# zadaca3.net
KiCad netlist of a schematic drawn in EAGLE
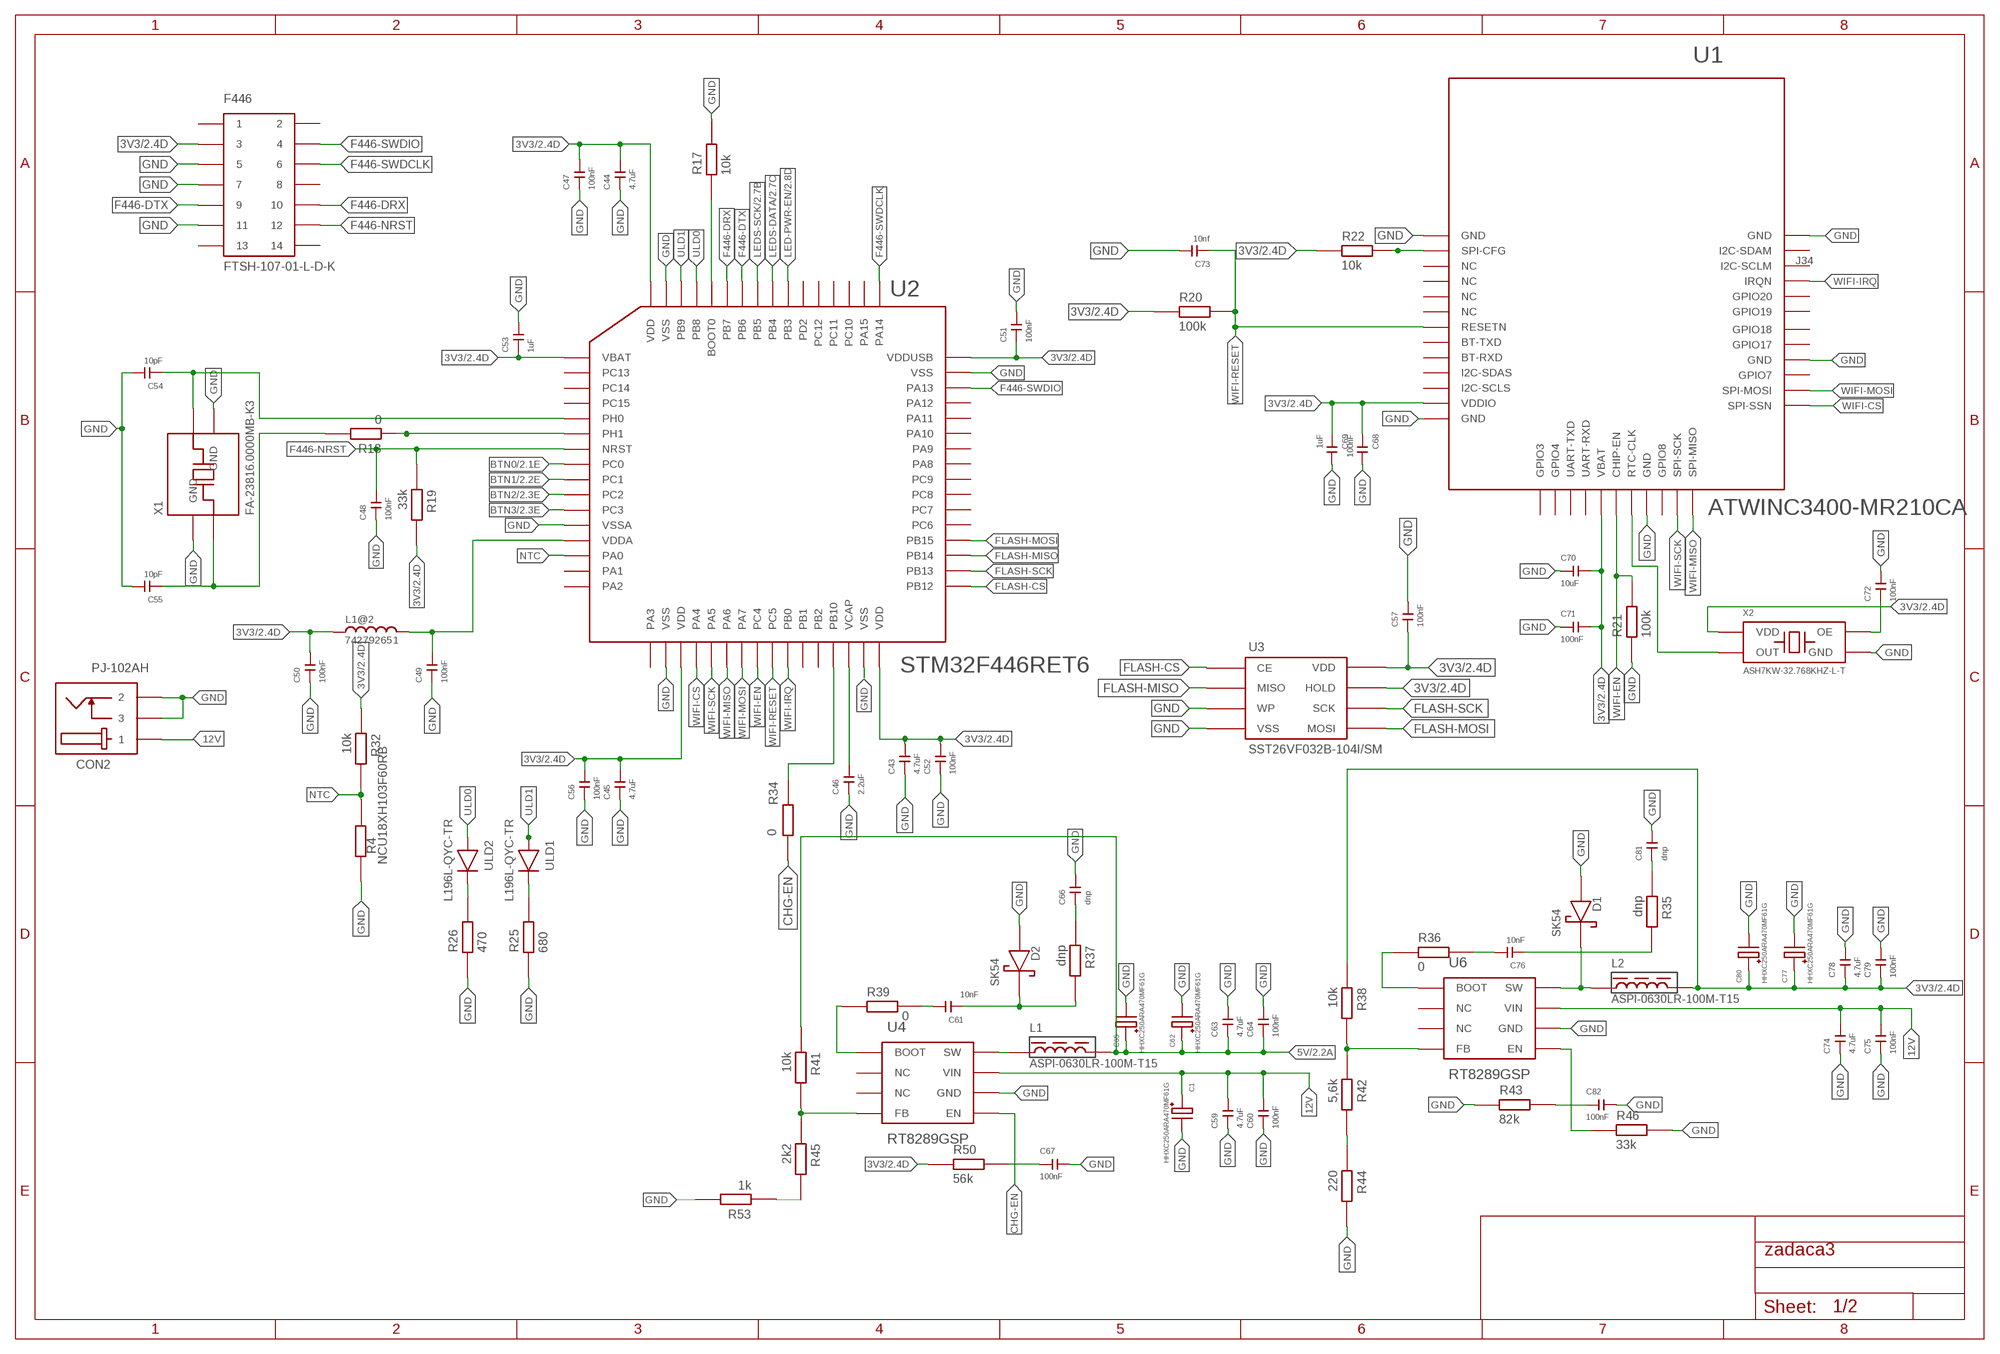
[diagram p0: schematic, sheet 1]
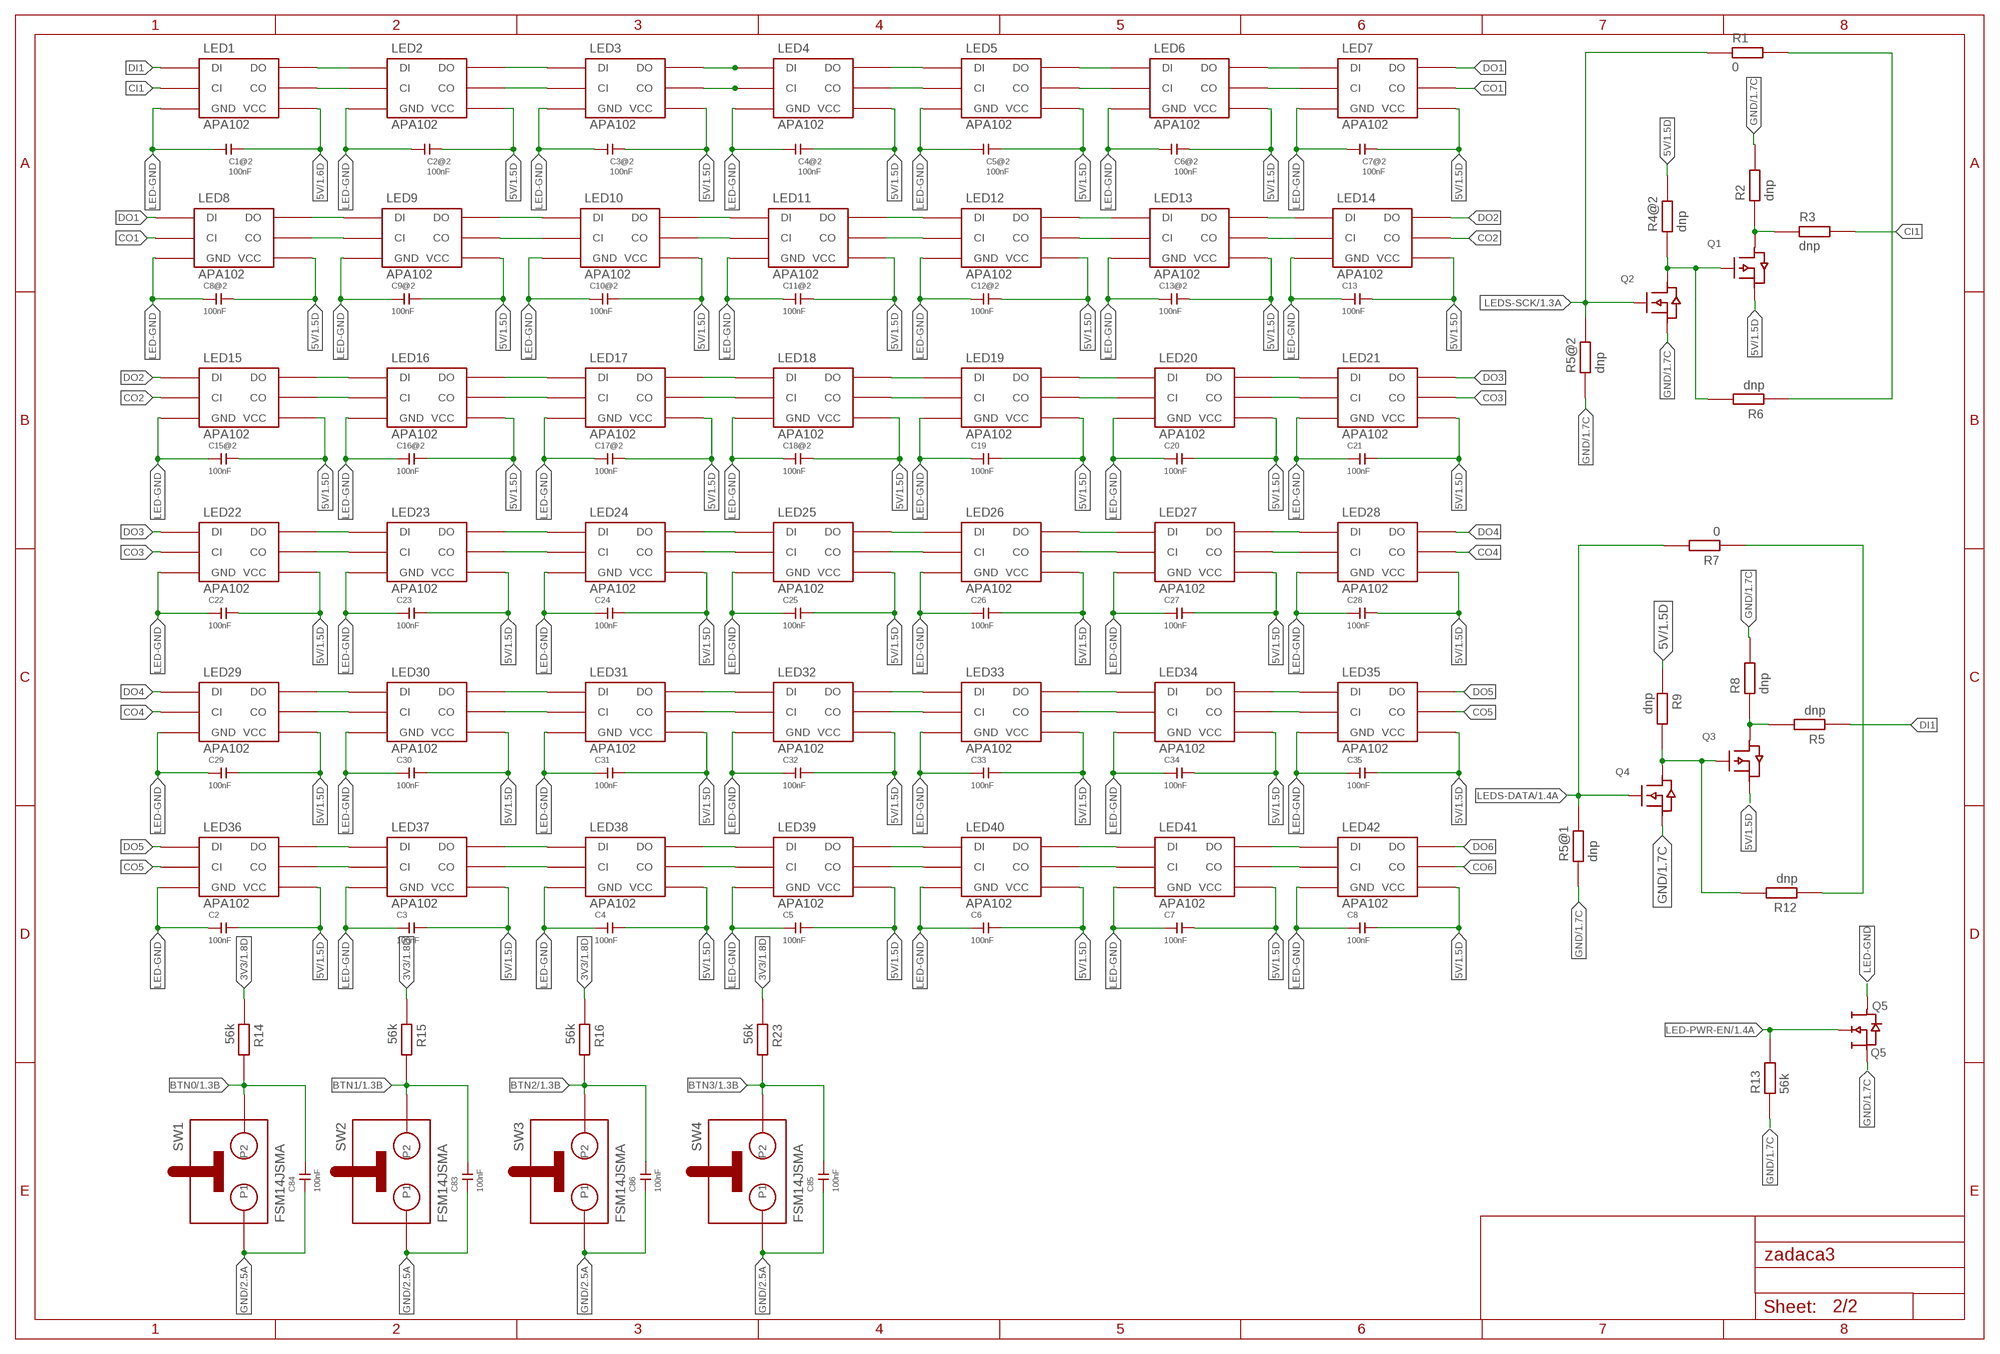
[diagram p1: schematic, sheet 2]

(export (version "E")
  (design (tool "Eeschema 10.0.6"))
  (components
    (comp (ref "C1")
      (value "HHXC250ARA470MF61G")
      (footprint "eagle-import:HHXC250ARA470MF61G")
      (libsource (lib "eagle-import") (part "HHXC250ARA470MF61G"))
    )
    (comp (ref "C43")
      (value "4.7uF")
      (footprint "eagle-import:CAPACITOR-0805-SMD")
      (libsource (lib "eagle-import") (part "CAPACITOR-0805-SMD"))
    )
    (comp (ref "C44")
      (value "4.7uF")
      (footprint "eagle-import:CAPACITOR-0805-SMD")
      (libsource (lib "eagle-import") (part "CAPACITOR-0805-SMD"))
    )
    (comp (ref "C45")
      (value "4.7uF")
      (footprint "eagle-import:CAPACITOR-0805-SMD")
      (libsource (lib "eagle-import") (part "CAPACITOR-0805-SMD"))
    )
    (comp (ref "C46")
      (value "2.2uF")
      (footprint "eagle-import:CAPACITOR-0805-SMD")
      (libsource (lib "eagle-import") (part "CAPACITOR-0805-SMD"))
    )
    (comp (ref "C47")
      (value "100nF")
      (footprint "eagle-import:CAPACITOR-0805-SMD")
      (libsource (lib "eagle-import") (part "CAPACITOR-0805-SMD"))
    )
    (comp (ref "C48")
      (value "100nF")
      (footprint "eagle-import:CAPACITOR-0805-SMD")
      (libsource (lib "eagle-import") (part "CAPACITOR-0805-SMD"))
    )
    (comp (ref "C49")
      (value "100nF")
      (footprint "eagle-import:CAPACITOR-0805-SMD")
      (libsource (lib "eagle-import") (part "CAPACITOR-0805-SMD"))
    )
    (comp (ref "C50")
      (value "100nF")
      (footprint "eagle-import:CAPACITOR-0805-SMD")
      (libsource (lib "eagle-import") (part "CAPACITOR-0805-SMD"))
    )
    (comp (ref "C51")
      (value "100nF")
      (footprint "eagle-import:CAPACITOR-0805-SMD")
      (libsource (lib "eagle-import") (part "CAPACITOR-0805-SMD"))
    )
    (comp (ref "C52")
      (value "100nF")
      (footprint "eagle-import:CAPACITOR-0805-SMD")
      (libsource (lib "eagle-import") (part "CAPACITOR-0805-SMD"))
    )
    (comp (ref "C53")
      (value "1uF")
      (footprint "eagle-import:CAPACITOR-0805-SMD")
      (libsource (lib "eagle-import") (part "CAPACITOR-0805-SMD"))
    )
    (comp (ref "C54")
      (value "10pF")
      (footprint "eagle-import:CAPACITOR-0805-SMD")
      (libsource (lib "eagle-import") (part "CAPACITOR-0805-SMD"))
    )
    (comp (ref "C55")
      (value "10pF")
      (footprint "eagle-import:CAPACITOR-0805-SMD")
      (libsource (lib "eagle-import") (part "CAPACITOR-0805-SMD"))
    )
    (comp (ref "C56")
      (value "100nF")
      (footprint "eagle-import:CAPACITOR-0805-SMD")
      (libsource (lib "eagle-import") (part "CAPACITOR-0805-SMD"))
    )
    (comp (ref "C57")
      (value "100nF")
      (footprint "eagle-import:CAPACITOR-0805-SMD")
      (libsource (lib "eagle-import") (part "CAPACITOR-0805-SMD"))
    )
    (comp (ref "C59")
      (value "4.7uF")
      (footprint "eagle-import:CAPACITOR-0805-SMD")
      (libsource (lib "eagle-import") (part "CAPACITOR-0805-SMD"))
    )
    (comp (ref "C60")
      (value "100nF")
      (footprint "eagle-import:CAPACITOR-0805-SMD")
      (libsource (lib "eagle-import") (part "CAPACITOR-0805-SMD"))
    )
    (comp (ref "C61")
      (value "10nF")
      (footprint "eagle-import:CAPACITOR-0805-SMD")
      (libsource (lib "eagle-import") (part "CAPACITOR-0805-SMD"))
    )
    (comp (ref "C62")
      (value "HHXC250ARA470MF61G")
      (footprint "eagle-import:HHXC250ARA470MF61G")
      (libsource (lib "eagle-import") (part "HHXC250ARA470MF61G"))
    )
    (comp (ref "C63")
      (value "4.7uF")
      (footprint "eagle-import:CAPACITOR-0805-SMD")
      (libsource (lib "eagle-import") (part "CAPACITOR-0805-SMD"))
    )
    (comp (ref "C64")
      (value "100nF")
      (footprint "eagle-import:CAPACITOR-0805-SMD")
      (libsource (lib "eagle-import") (part "CAPACITOR-0805-SMD"))
    )
    (comp (ref "C65")
      (value "HHXC250ARA470MF61G")
      (footprint "eagle-import:HHXC250ARA470MF61G")
      (libsource (lib "eagle-import") (part "HHXC250ARA470MF61G"))
    )
    (comp (ref "C66")
      (value "dnp")
      (footprint "eagle-import:CAPACITOR-0805-SMD")
      (libsource (lib "eagle-import") (part "CAPACITOR-0805-SMD"))
    )
    (comp (ref "C67")
      (value "100nF")
      (footprint "eagle-import:CAPACITOR-0805-SMD")
      (libsource (lib "eagle-import") (part "CAPACITOR-0805-SMD"))
    )
    (comp (ref "C68")
      (value "100nF")
      (footprint "eagle-import:CAPACITOR-0805-SMD")
      (libsource (lib "eagle-import") (part "CAPACITOR-0805-SMD"))
    )
    (comp (ref "C69")
      (value "1uF")
      (footprint "eagle-import:CAPACITOR-0805-SMD")
      (libsource (lib "eagle-import") (part "CAPACITOR-0805-SMD"))
    )
    (comp (ref "C70")
      (value "10uF")
      (footprint "eagle-import:CAPACITOR-0805-SMD")
      (libsource (lib "eagle-import") (part "CAPACITOR-0805-SMD"))
    )
    (comp (ref "C71")
      (value "100nF")
      (footprint "eagle-import:CAPACITOR-0805-SMD")
      (libsource (lib "eagle-import") (part "CAPACITOR-0805-SMD"))
    )
    (comp (ref "C72")
      (value "100nF")
      (footprint "eagle-import:CAPACITOR-0805-SMD")
      (libsource (lib "eagle-import") (part "CAPACITOR-0805-SMD"))
    )
    (comp (ref "C73")
      (value "10nf")
      (footprint "eagle-import:CAPACITOR-0805-SMD")
      (libsource (lib "eagle-import") (part "CAPACITOR-0805-SMD"))
    )
    (comp (ref "C74")
      (value "4.7uF")
      (footprint "eagle-import:CAPACITOR-0805-SMD")
      (libsource (lib "eagle-import") (part "CAPACITOR-0805-SMD"))
    )
    (comp (ref "C75")
      (value "100nF")
      (footprint "eagle-import:CAPACITOR-0805-SMD")
      (libsource (lib "eagle-import") (part "CAPACITOR-0805-SMD"))
    )
    (comp (ref "C76")
      (value "10nF")
      (footprint "eagle-import:CAPACITOR-0805-SMD")
      (libsource (lib "eagle-import") (part "CAPACITOR-0805-SMD"))
    )
    (comp (ref "C77")
      (value "HHXC250ARA470MF61G")
      (footprint "eagle-import:HHXC250ARA470MF61G")
      (libsource (lib "eagle-import") (part "HHXC250ARA470MF61G"))
    )
    (comp (ref "C78")
      (value "4.7uF")
      (footprint "eagle-import:CAPACITOR-0805-SMD")
      (libsource (lib "eagle-import") (part "CAPACITOR-0805-SMD"))
    )
    (comp (ref "C79")
      (value "100nF")
      (footprint "eagle-import:CAPACITOR-0805-SMD")
      (libsource (lib "eagle-import") (part "CAPACITOR-0805-SMD"))
    )
    (comp (ref "C80")
      (value "HHXC250ARA470MF61G")
      (footprint "eagle-import:HHXC250ARA470MF61G")
      (libsource (lib "eagle-import") (part "HHXC250ARA470MF61G"))
    )
    (comp (ref "C81")
      (value "dnp")
      (footprint "eagle-import:CAPACITOR-0805-SMD")
      (libsource (lib "eagle-import") (part "CAPACITOR-0805-SMD"))
    )
    (comp (ref "C82")
      (value "100nF")
      (footprint "eagle-import:CAPACITOR-0805-SMD")
      (libsource (lib "eagle-import") (part "CAPACITOR-0805-SMD"))
    )
    (comp (ref "CON2")
      (value "PJ-102AH")
      (footprint "eagle-import:PJ-102AH")
      (libsource (lib "eagle-import") (part "PJ-102AH"))
    )
    (comp (ref "D1")
      (value "SK54")
      (footprint "eagle-import:SK54")
      (libsource (lib "eagle-import") (part "SK54"))
    )
    (comp (ref "D2")
      (value "SK54")
      (footprint "eagle-import:SK54")
      (libsource (lib "eagle-import") (part "SK54"))
    )
    (comp (ref "F446")
      (value "FTSH-107-01-L-D-K")
      (footprint "eagle-import:FTSH-107-01-L-D-K")
      (libsource (lib "eagle-import") (part "FTSH-107-01-L-D-K"))
    )
    (comp (ref "L1")
      (value "ASPI-0630LR-100M-T15")
      (footprint "eagle-import:ASPI-0630LR-100M-T15")
      (libsource (lib "eagle-import") (part "ASPI-0630LR-100M-T15"))
    )
    (comp (ref "L1@2")
      (value "742792651")
      (footprint "eagle-import:742792651")
      (libsource (lib "eagle-import") (part "742792651"))
    )
    (comp (ref "L2")
      (value "ASPI-0630LR-100M-T15")
      (footprint "eagle-import:ASPI-0630LR-100M-T15")
      (libsource (lib "eagle-import") (part "ASPI-0630LR-100M-T15"))
    )
    (comp (ref "R4")
      (value "NCU18XH103F60RB")
      (footprint "eagle-import:NCU18XH103F60RB")
      (libsource (lib "eagle-import") (part "NCU18XH103F60RB"))
    )
    (comp (ref "R17")
      (value "10k")
      (footprint "eagle-import:RESISTOR-0805-SMD")
      (libsource (lib "eagle-import") (part "RESISTOR-0805-SMD"))
    )
    (comp (ref "R18")
      (value "0")
      (footprint "eagle-import:RESISTOR-0805-SMD")
      (libsource (lib "eagle-import") (part "RESISTOR-0805-SMD"))
    )
    (comp (ref "R19")
      (value "33k")
      (footprint "eagle-import:RESISTOR-0805-SMD")
      (libsource (lib "eagle-import") (part "RESISTOR-0805-SMD"))
    )
    (comp (ref "R20")
      (value "100k")
      (footprint "eagle-import:RESISTOR-0805-SMD")
      (libsource (lib "eagle-import") (part "RESISTOR-0805-SMD"))
    )
    (comp (ref "R21")
      (value "100k")
      (footprint "eagle-import:RESISTOR-0805-SMD")
      (libsource (lib "eagle-import") (part "RESISTOR-0805-SMD"))
    )
    (comp (ref "R22")
      (value "10k")
      (footprint "eagle-import:RESISTOR-0805-SMD")
      (libsource (lib "eagle-import") (part "RESISTOR-0805-SMD"))
    )
    (comp (ref "R25")
      (value "680")
      (footprint "eagle-import:RESISTOR-0805-SMD")
      (libsource (lib "eagle-import") (part "RESISTOR-0805-SMD"))
    )
    (comp (ref "R26")
      (value "470")
      (footprint "eagle-import:RESISTOR-0805-SMD")
      (libsource (lib "eagle-import") (part "RESISTOR-0805-SMD"))
    )
    (comp (ref "R32")
      (value "10k")
      (footprint "eagle-import:RESISTOR-0805-SMD")
      (libsource (lib "eagle-import") (part "RESISTOR-0805-SMD"))
    )
    (comp (ref "R34")
      (value "0")
      (footprint "eagle-import:RESISTOR-0805-SMD")
      (libsource (lib "eagle-import") (part "RESISTOR-0805-SMD"))
    )
    (comp (ref "R35")
      (value "dnp")
      (footprint "eagle-import:RESISTOR-0805-SMD")
      (libsource (lib "eagle-import") (part "RESISTOR-0805-SMD"))
    )
    (comp (ref "R36")
      (value "0")
      (footprint "eagle-import:RESISTOR-0805-SMD")
      (libsource (lib "eagle-import") (part "RESISTOR-0805-SMD"))
    )
    (comp (ref "R37")
      (value "dnp")
      (footprint "eagle-import:RESISTOR-0805-SMD")
      (libsource (lib "eagle-import") (part "RESISTOR-0805-SMD"))
    )
    (comp (ref "R38")
      (value "10k")
      (footprint "eagle-import:RESISTOR-0805-SMD")
      (libsource (lib "eagle-import") (part "RESISTOR-0805-SMD"))
    )
    (comp (ref "R39")
      (value "0")
      (footprint "eagle-import:RESISTOR-0805-SMD")
      (libsource (lib "eagle-import") (part "RESISTOR-0805-SMD"))
    )
    (comp (ref "R41")
      (value "10k")
      (footprint "eagle-import:RESISTOR-0805-SMD")
      (libsource (lib "eagle-import") (part "RESISTOR-0805-SMD"))
    )
    (comp (ref "R42")
      (value "5,6k")
      (footprint "eagle-import:RESISTOR-0805-SMD")
      (libsource (lib "eagle-import") (part "RESISTOR-0805-SMD"))
    )
    (comp (ref "R43")
      (value "82k")
      (footprint "eagle-import:RESISTOR-0805-SMD")
      (libsource (lib "eagle-import") (part "RESISTOR-0805-SMD"))
    )
    (comp (ref "R44")
      (value "220")
      (footprint "eagle-import:RESISTOR-0805-SMD")
      (libsource (lib "eagle-import") (part "RESISTOR-0805-SMD"))
    )
    (comp (ref "R45")
      (value "2k2")
      (footprint "eagle-import:RESISTOR-0805-SMD")
      (libsource (lib "eagle-import") (part "RESISTOR-0805-SMD"))
    )
    (comp (ref "R46")
      (value "33k")
      (footprint "eagle-import:RESISTOR-0805-SMD")
      (libsource (lib "eagle-import") (part "RESISTOR-0805-SMD"))
    )
    (comp (ref "R50")
      (value "56k")
      (footprint "eagle-import:RESISTOR-0805-SMD")
      (libsource (lib "eagle-import") (part "RESISTOR-0805-SMD"))
    )
    (comp (ref "R53")
      (value "1k")
      (footprint "eagle-import:RESISTOR-0805-SMD")
      (libsource (lib "eagle-import") (part "RESISTOR-0805-SMD"))
    )
    (comp (ref "U1")
      (value "ATWINC3400-MR210CA")
      (footprint "eagle-import:ATWINC3400-MR210CA")
      (libsource (lib "eagle-import") (part "ATWINC3400-MR210CA"))
    )
    (comp (ref "U2")
      (value "STM32F446RET6")
      (footprint "eagle-import:STM32F446RET6")
      (libsource (lib "eagle-import") (part "STM32F446RET6"))
    )
    (comp (ref "U3")
      (value "SST26VF032B-104I/SM")
      (footprint "eagle-import:SST26VF032B-104I_SM")
      (libsource (lib "eagle-import") (part "SST26VF032B-104I/SM"))
    )
    (comp (ref "U4")
      (value "RT8289GSP")
      (footprint "eagle-import:RT8289GSP")
      (libsource (lib "eagle-import") (part "RT8289GSP"))
    )
    (comp (ref "U6")
      (value "RT8289GSP")
      (footprint "eagle-import:RT8289GSP")
      (libsource (lib "eagle-import") (part "RT8289GSP"))
    )
    (comp (ref "ULD1")
      (value "L196L-QYC-TR")
      (footprint "eagle-import:L196L-QYC-TR")
      (libsource (lib "eagle-import") (part "L196L-QYC-TR"))
    )
    (comp (ref "ULD2")
      (value "L196L-QYC-TR")
      (footprint "eagle-import:L196L-QYC-TR")
      (libsource (lib "eagle-import") (part "L196L-QYC-TR"))
    )
    (comp (ref "X1")
      (value "FA-23816.0000MB-K3")
      (footprint "eagle-import:FA-23816.0000MB-K3")
      (libsource (lib "eagle-import") (part "FA-23816.0000MB-K3"))
    )
    (comp (ref "X2")
      (value "ASH7KW-32.768KHZ-L-T")
      (footprint "eagle-import:ASH7KW-32.768KHZ-L-T")
      (libsource (lib "eagle-import") (part "ASH7KW-32.768KHZ-L-T"))
    )
    (comp (ref "C1@2")
      (value "100nF")
      (footprint "eagle-import:CAPACITOR-0805-SMD")
      (libsource (lib "eagle-import") (part "CAPACITOR-0805-SMD"))
    )
    (comp (ref "C2")
      (value "100nF")
      (footprint "eagle-import:CAPACITOR-0805-SMD")
      (libsource (lib "eagle-import") (part "CAPACITOR-0805-SMD"))
    )
    (comp (ref "C2@2")
      (value "100nF")
      (footprint "eagle-import:CAPACITOR-0805-SMD")
      (libsource (lib "eagle-import") (part "CAPACITOR-0805-SMD"))
    )
    (comp (ref "C3")
      (value "100nF")
      (footprint "eagle-import:CAPACITOR-0805-SMD")
      (libsource (lib "eagle-import") (part "CAPACITOR-0805-SMD"))
    )
    (comp (ref "C3@2")
      (value "100nF")
      (footprint "eagle-import:CAPACITOR-0805-SMD")
      (libsource (lib "eagle-import") (part "CAPACITOR-0805-SMD"))
    )
    (comp (ref "C4")
      (value "100nF")
      (footprint "eagle-import:CAPACITOR-0805-SMD")
      (libsource (lib "eagle-import") (part "CAPACITOR-0805-SMD"))
    )
    (comp (ref "C4@2")
      (value "100nF")
      (footprint "eagle-import:CAPACITOR-0805-SMD")
      (libsource (lib "eagle-import") (part "CAPACITOR-0805-SMD"))
    )
    (comp (ref "C5")
      (value "100nF")
      (footprint "eagle-import:CAPACITOR-0805-SMD")
      (libsource (lib "eagle-import") (part "CAPACITOR-0805-SMD"))
    )
    (comp (ref "C5@2")
      (value "100nF")
      (footprint "eagle-import:CAPACITOR-0805-SMD")
      (libsource (lib "eagle-import") (part "CAPACITOR-0805-SMD"))
    )
    (comp (ref "C6")
      (value "100nF")
      (footprint "eagle-import:CAPACITOR-0805-SMD")
      (libsource (lib "eagle-import") (part "CAPACITOR-0805-SMD"))
    )
    (comp (ref "C6@2")
      (value "100nF")
      (footprint "eagle-import:CAPACITOR-0805-SMD")
      (libsource (lib "eagle-import") (part "CAPACITOR-0805-SMD"))
    )
    (comp (ref "C7")
      (value "100nF")
      (footprint "eagle-import:CAPACITOR-0805-SMD")
      (libsource (lib "eagle-import") (part "CAPACITOR-0805-SMD"))
    )
    (comp (ref "C7@2")
      (value "100nF")
      (footprint "eagle-import:CAPACITOR-0805-SMD")
      (libsource (lib "eagle-import") (part "CAPACITOR-0805-SMD"))
    )
    (comp (ref "C8")
      (value "100nF")
      (footprint "eagle-import:CAPACITOR-0805-SMD")
      (libsource (lib "eagle-import") (part "CAPACITOR-0805-SMD"))
    )
    (comp (ref "C8@2")
      (value "100nF")
      (footprint "eagle-import:CAPACITOR-0805-SMD")
      (libsource (lib "eagle-import") (part "CAPACITOR-0805-SMD"))
    )
    (comp (ref "C9@2")
      (value "100nF")
      (footprint "eagle-import:CAPACITOR-0805-SMD")
      (libsource (lib "eagle-import") (part "CAPACITOR-0805-SMD"))
    )
    (comp (ref "C10@2")
      (value "100nF")
      (footprint "eagle-import:CAPACITOR-0805-SMD")
      (libsource (lib "eagle-import") (part "CAPACITOR-0805-SMD"))
    )
    (comp (ref "C11@2")
      (value "100nF")
      (footprint "eagle-import:CAPACITOR-0805-SMD")
      (libsource (lib "eagle-import") (part "CAPACITOR-0805-SMD"))
    )
    (comp (ref "C12@2")
      (value "100nF")
      (footprint "eagle-import:CAPACITOR-0805-SMD")
      (libsource (lib "eagle-import") (part "CAPACITOR-0805-SMD"))
    )
    (comp (ref "C13")
      (value "100nF")
      (footprint "eagle-import:CAPACITOR-0805-SMD")
      (libsource (lib "eagle-import") (part "CAPACITOR-0805-SMD"))
    )
    (comp (ref "C13@2")
      (value "100nF")
      (footprint "eagle-import:CAPACITOR-0805-SMD")
      (libsource (lib "eagle-import") (part "CAPACITOR-0805-SMD"))
    )
    (comp (ref "C15@2")
      (value "100nF")
      (footprint "eagle-import:CAPACITOR-0805-SMD")
      (libsource (lib "eagle-import") (part "CAPACITOR-0805-SMD"))
    )
    (comp (ref "C16@2")
      (value "100nF")
      (footprint "eagle-import:CAPACITOR-0805-SMD")
      (libsource (lib "eagle-import") (part "CAPACITOR-0805-SMD"))
    )
    (comp (ref "C17@2")
      (value "100nF")
      (footprint "eagle-import:CAPACITOR-0805-SMD")
      (libsource (lib "eagle-import") (part "CAPACITOR-0805-SMD"))
    )
    (comp (ref "C18@2")
      (value "100nF")
      (footprint "eagle-import:CAPACITOR-0805-SMD")
      (libsource (lib "eagle-import") (part "CAPACITOR-0805-SMD"))
    )
    (comp (ref "C19")
      (value "100nF")
      (footprint "eagle-import:CAPACITOR-0805-SMD")
      (libsource (lib "eagle-import") (part "CAPACITOR-0805-SMD"))
    )
    (comp (ref "C20")
      (value "100nF")
      (footprint "eagle-import:CAPACITOR-0805-SMD")
      (libsource (lib "eagle-import") (part "CAPACITOR-0805-SMD"))
    )
    (comp (ref "C21")
      (value "100nF")
      (footprint "eagle-import:CAPACITOR-0805-SMD")
      (libsource (lib "eagle-import") (part "CAPACITOR-0805-SMD"))
    )
    (comp (ref "C22")
      (value "100nF")
      (footprint "eagle-import:CAPACITOR-0805-SMD")
      (libsource (lib "eagle-import") (part "CAPACITOR-0805-SMD"))
    )
    (comp (ref "C23")
      (value "100nF")
      (footprint "eagle-import:CAPACITOR-0805-SMD")
      (libsource (lib "eagle-import") (part "CAPACITOR-0805-SMD"))
    )
    (comp (ref "C24")
      (value "100nF")
      (footprint "eagle-import:CAPACITOR-0805-SMD")
      (libsource (lib "eagle-import") (part "CAPACITOR-0805-SMD"))
    )
    (comp (ref "C25")
      (value "100nF")
      (footprint "eagle-import:CAPACITOR-0805-SMD")
      (libsource (lib "eagle-import") (part "CAPACITOR-0805-SMD"))
    )
    (comp (ref "C26")
      (value "100nF")
      (footprint "eagle-import:CAPACITOR-0805-SMD")
      (libsource (lib "eagle-import") (part "CAPACITOR-0805-SMD"))
    )
    (comp (ref "C27")
      (value "100nF")
      (footprint "eagle-import:CAPACITOR-0805-SMD")
      (libsource (lib "eagle-import") (part "CAPACITOR-0805-SMD"))
    )
    (comp (ref "C28")
      (value "100nF")
      (footprint "eagle-import:CAPACITOR-0805-SMD")
      (libsource (lib "eagle-import") (part "CAPACITOR-0805-SMD"))
    )
    (comp (ref "C29")
      (value "100nF")
      (footprint "eagle-import:CAPACITOR-0805-SMD")
      (libsource (lib "eagle-import") (part "CAPACITOR-0805-SMD"))
    )
    (comp (ref "C30")
      (value "100nF")
      (footprint "eagle-import:CAPACITOR-0805-SMD")
      (libsource (lib "eagle-import") (part "CAPACITOR-0805-SMD"))
    )
    (comp (ref "C31")
      (value "100nF")
      (footprint "eagle-import:CAPACITOR-0805-SMD")
      (libsource (lib "eagle-import") (part "CAPACITOR-0805-SMD"))
    )
    (comp (ref "C32")
      (value "100nF")
      (footprint "eagle-import:CAPACITOR-0805-SMD")
      (libsource (lib "eagle-import") (part "CAPACITOR-0805-SMD"))
    )
    (comp (ref "C33")
      (value "100nF")
      (footprint "eagle-import:CAPACITOR-0805-SMD")
      (libsource (lib "eagle-import") (part "CAPACITOR-0805-SMD"))
    )
    (comp (ref "C34")
      (value "100nF")
      (footprint "eagle-import:CAPACITOR-0805-SMD")
      (libsource (lib "eagle-import") (part "CAPACITOR-0805-SMD"))
    )
    (comp (ref "C35")
      (value "100nF")
      (footprint "eagle-import:CAPACITOR-0805-SMD")
      (libsource (lib "eagle-import") (part "CAPACITOR-0805-SMD"))
    )
    (comp (ref "C83")
      (value "100nF")
      (footprint "eagle-import:CAPACITOR-0805-SMD")
      (libsource (lib "eagle-import") (part "CAPACITOR-0805-SMD"))
    )
    (comp (ref "C84")
      (value "100nF")
      (footprint "eagle-import:CAPACITOR-0805-SMD")
      (libsource (lib "eagle-import") (part "CAPACITOR-0805-SMD"))
    )
    (comp (ref "C85")
      (value "100nF")
      (footprint "eagle-import:CAPACITOR-0805-SMD")
      (libsource (lib "eagle-import") (part "CAPACITOR-0805-SMD"))
    )
    (comp (ref "C86")
      (value "100nF")
      (footprint "eagle-import:CAPACITOR-0805-SMD")
      (libsource (lib "eagle-import") (part "CAPACITOR-0805-SMD"))
    )
    (comp (ref "LED1")
      (value "APA102")
      (footprint "eagle-import:APA102")
      (libsource (lib "eagle-import") (part "APA102"))
    )
    (comp (ref "LED2")
      (value "APA102")
      (footprint "eagle-import:APA102")
      (libsource (lib "eagle-import") (part "APA102"))
    )
    (comp (ref "LED3")
      (value "APA102")
      (footprint "eagle-import:APA102")
      (libsource (lib "eagle-import") (part "APA102"))
    )
    (comp (ref "LED4")
      (value "APA102")
      (footprint "eagle-import:APA102")
      (libsource (lib "eagle-import") (part "APA102"))
    )
    (comp (ref "LED5")
      (value "APA102")
      (footprint "eagle-import:APA102")
      (libsource (lib "eagle-import") (part "APA102"))
    )
    (comp (ref "LED6")
      (value "APA102")
      (footprint "eagle-import:APA102")
      (libsource (lib "eagle-import") (part "APA102"))
    )
    (comp (ref "LED7")
      (value "APA102")
      (footprint "eagle-import:APA102")
      (libsource (lib "eagle-import") (part "APA102"))
    )
    (comp (ref "LED8")
      (value "APA102")
      (footprint "eagle-import:APA102")
      (libsource (lib "eagle-import") (part "APA102"))
    )
    (comp (ref "LED9")
      (value "APA102")
      (footprint "eagle-import:APA102")
      (libsource (lib "eagle-import") (part "APA102"))
    )
    (comp (ref "LED10")
      (value "APA102")
      (footprint "eagle-import:APA102")
      (libsource (lib "eagle-import") (part "APA102"))
    )
    (comp (ref "LED11")
      (value "APA102")
      (footprint "eagle-import:APA102")
      (libsource (lib "eagle-import") (part "APA102"))
    )
    (comp (ref "LED12")
      (value "APA102")
      (footprint "eagle-import:APA102")
      (libsource (lib "eagle-import") (part "APA102"))
    )
    (comp (ref "LED13")
      (value "APA102")
      (footprint "eagle-import:APA102")
      (libsource (lib "eagle-import") (part "APA102"))
    )
    (comp (ref "LED14")
      (value "APA102")
      (footprint "eagle-import:APA102")
      (libsource (lib "eagle-import") (part "APA102"))
    )
    (comp (ref "LED15")
      (value "APA102")
      (footprint "eagle-import:APA102")
      (libsource (lib "eagle-import") (part "APA102"))
    )
    (comp (ref "LED16")
      (value "APA102")
      (footprint "eagle-import:APA102")
      (libsource (lib "eagle-import") (part "APA102"))
    )
    (comp (ref "LED17")
      (value "APA102")
      (footprint "eagle-import:APA102")
      (libsource (lib "eagle-import") (part "APA102"))
    )
    (comp (ref "LED18")
      (value "APA102")
      (footprint "eagle-import:APA102")
      (libsource (lib "eagle-import") (part "APA102"))
    )
    (comp (ref "LED19")
      (value "APA102")
      (footprint "eagle-import:APA102")
      (libsource (lib "eagle-import") (part "APA102"))
    )
    (comp (ref "LED20")
      (value "APA102")
      (footprint "eagle-import:APA102")
      (libsource (lib "eagle-import") (part "APA102"))
    )
    (comp (ref "LED21")
      (value "APA102")
      (footprint "eagle-import:APA102")
      (libsource (lib "eagle-import") (part "APA102"))
    )
    (comp (ref "LED22")
      (value "APA102")
      (footprint "eagle-import:APA102")
      (libsource (lib "eagle-import") (part "APA102"))
    )
    (comp (ref "LED23")
      (value "APA102")
      (footprint "eagle-import:APA102")
      (libsource (lib "eagle-import") (part "APA102"))
    )
    (comp (ref "LED24")
      (value "APA102")
      (footprint "eagle-import:APA102")
      (libsource (lib "eagle-import") (part "APA102"))
    )
    (comp (ref "LED25")
      (value "APA102")
      (footprint "eagle-import:APA102")
      (libsource (lib "eagle-import") (part "APA102"))
    )
    (comp (ref "LED26")
      (value "APA102")
      (footprint "eagle-import:APA102")
      (libsource (lib "eagle-import") (part "APA102"))
    )
    (comp (ref "LED27")
      (value "APA102")
      (footprint "eagle-import:APA102")
      (libsource (lib "eagle-import") (part "APA102"))
    )
    (comp (ref "LED28")
      (value "APA102")
      (footprint "eagle-import:APA102")
      (libsource (lib "eagle-import") (part "APA102"))
    )
    (comp (ref "LED29")
      (value "APA102")
      (footprint "eagle-import:APA102")
      (libsource (lib "eagle-import") (part "APA102"))
    )
    (comp (ref "LED30")
      (value "APA102")
      (footprint "eagle-import:APA102")
      (libsource (lib "eagle-import") (part "APA102"))
    )
    (comp (ref "LED31")
      (value "APA102")
      (footprint "eagle-import:APA102")
      (libsource (lib "eagle-import") (part "APA102"))
    )
    (comp (ref "LED32")
      (value "APA102")
      (footprint "eagle-import:APA102")
      (libsource (lib "eagle-import") (part "APA102"))
    )
    (comp (ref "LED33")
      (value "APA102")
      (footprint "eagle-import:APA102")
      (libsource (lib "eagle-import") (part "APA102"))
    )
    (comp (ref "LED34")
      (value "APA102")
      (footprint "eagle-import:APA102")
      (libsource (lib "eagle-import") (part "APA102"))
    )
    (comp (ref "LED35")
      (value "APA102")
      (footprint "eagle-import:APA102")
      (libsource (lib "eagle-import") (part "APA102"))
    )
    (comp (ref "LED36")
      (value "APA102")
      (footprint "eagle-import:APA102")
      (libsource (lib "eagle-import") (part "APA102"))
    )
    (comp (ref "LED37")
      (value "APA102")
      (footprint "eagle-import:APA102")
      (libsource (lib "eagle-import") (part "APA102"))
    )
    (comp (ref "LED38")
      (value "APA102")
      (footprint "eagle-import:APA102")
      (libsource (lib "eagle-import") (part "APA102"))
    )
    (comp (ref "LED39")
      (value "APA102")
      (footprint "eagle-import:APA102")
      (libsource (lib "eagle-import") (part "APA102"))
    )
    (comp (ref "LED40")
      (value "APA102")
      (footprint "eagle-import:APA102")
      (libsource (lib "eagle-import") (part "APA102"))
    )
    (comp (ref "LED41")
      (value "APA102")
      (footprint "eagle-import:APA102")
      (libsource (lib "eagle-import") (part "APA102"))
    )
    (comp (ref "LED42")
      (value "APA102")
      (footprint "eagle-import:APA102")
      (libsource (lib "eagle-import") (part "APA102"))
    )
    (comp (ref "Q1")
      (value "NPN")
      (footprint "eagle-import:NPN")
      (libsource (lib "eagle-import") (part "NPN"))
    )
    (comp (ref "Q2")
      (value "PNP")
      (footprint "eagle-import:PNP")
      (libsource (lib "eagle-import") (part "PNP"))
    )
    (comp (ref "Q3")
      (value "NPN")
      (footprint "eagle-import:NPN")
      (libsource (lib "eagle-import") (part "NPN"))
    )
    (comp (ref "Q4")
      (value "PNP")
      (footprint "eagle-import:PNP")
      (libsource (lib "eagle-import") (part "PNP"))
    )
    (comp (ref "Q5")
      (value "DMN6068LK3-13")
      (footprint "eagle-import:DMN6068LK3-13")
      (libsource (lib "eagle-import") (part "DMN6068LK3-13"))
    )
    (comp (ref "R1")
      (value "0")
      (footprint "eagle-import:RESISTOR-0805-SMD")
      (libsource (lib "eagle-import") (part "RESISTOR-0805-SMD"))
    )
    (comp (ref "R2")
      (value "dnp")
      (footprint "eagle-import:RESISTOR-0805-SMD")
      (libsource (lib "eagle-import") (part "RESISTOR-0805-SMD"))
    )
    (comp (ref "R3")
      (value "dnp")
      (footprint "eagle-import:RESISTOR-0805-SMD")
      (libsource (lib "eagle-import") (part "RESISTOR-0805-SMD"))
    )
    (comp (ref "R4@2")
      (value "dnp")
      (footprint "eagle-import:RESISTOR-0805-SMD")
      (libsource (lib "eagle-import") (part "RESISTOR-0805-SMD"))
    )
    (comp (ref "R5")
      (value "dnp")
      (footprint "eagle-import:RESISTOR-0805-SMD")
      (libsource (lib "eagle-import") (part "RESISTOR-0805-SMD"))
    )
    (comp (ref "R5@1")
      (value "dnp")
      (footprint "eagle-import:RESISTOR-0805-SMD")
      (libsource (lib "eagle-import") (part "RESISTOR-0805-SMD"))
    )
    (comp (ref "R5@2")
      (value "dnp")
      (footprint "eagle-import:RESISTOR-0805-SMD")
      (libsource (lib "eagle-import") (part "RESISTOR-0805-SMD"))
    )
    (comp (ref "R6")
      (value "dnp")
      (footprint "eagle-import:RESISTOR-0805-SMD")
      (libsource (lib "eagle-import") (part "RESISTOR-0805-SMD"))
    )
    (comp (ref "R7")
      (value "0")
      (footprint "eagle-import:RESISTOR-0805-SMD")
      (libsource (lib "eagle-import") (part "RESISTOR-0805-SMD"))
    )
    (comp (ref "R8")
      (value "dnp")
      (footprint "eagle-import:RESISTOR-0805-SMD")
      (libsource (lib "eagle-import") (part "RESISTOR-0805-SMD"))
    )
    (comp (ref "R9")
      (value "dnp")
      (footprint "eagle-import:RESISTOR-0805-SMD")
      (libsource (lib "eagle-import") (part "RESISTOR-0805-SMD"))
    )
    (comp (ref "R12")
      (value "dnp")
      (footprint "eagle-import:RESISTOR-0805-SMD")
      (libsource (lib "eagle-import") (part "RESISTOR-0805-SMD"))
    )
    (comp (ref "R13")
      (value "56k")
      (footprint "eagle-import:RESISTOR-0805-SMD")
      (libsource (lib "eagle-import") (part "RESISTOR-0805-SMD"))
    )
    (comp (ref "R14")
      (value "56k")
      (footprint "eagle-import:RESISTOR-0805-SMD")
      (libsource (lib "eagle-import") (part "RESISTOR-0805-SMD"))
    )
    (comp (ref "R15")
      (value "56k")
      (footprint "eagle-import:RESISTOR-0805-SMD")
      (libsource (lib "eagle-import") (part "RESISTOR-0805-SMD"))
    )
    (comp (ref "R16")
      (value "56k")
      (footprint "eagle-import:RESISTOR-0805-SMD")
      (libsource (lib "eagle-import") (part "RESISTOR-0805-SMD"))
    )
    (comp (ref "R23")
      (value "56k")
      (footprint "eagle-import:RESISTOR-0805-SMD")
      (libsource (lib "eagle-import") (part "RESISTOR-0805-SMD"))
    )
    (comp (ref "SW1")
      (value "FSM14JSMA")
      (footprint "eagle-import:FSM14JSMAS")
      (libsource (lib "eagle-import") (part "FSM14JSMA"))
    )
    (comp (ref "SW2")
      (value "FSM14JSMA")
      (footprint "eagle-import:FSM14JSMAS")
      (libsource (lib "eagle-import") (part "FSM14JSMA"))
    )
    (comp (ref "SW3")
      (value "FSM14JSMA")
      (footprint "eagle-import:FSM14JSMAS")
      (libsource (lib "eagle-import") (part "FSM14JSMA"))
    )
    (comp (ref "SW4")
      (value "FSM14JSMA")
      (footprint "eagle-import:FSM14JSMAS")
      (libsource (lib "eagle-import") (part "FSM14JSMA"))
    )
  )
  (nets
    (net (code "1") (name "3V3") (class "Default")
      (node (ref "C43") (pin "P2") (pinfunction "P2_P2") (pintype "bidirectional"))
      (node (ref "C44") (pin "P2") (pinfunction "P2_P2") (pintype "bidirectional"))
      (node (ref "C45") (pin "P2") (pinfunction "P2_P2") (pintype "bidirectional"))
      (node (ref "C47") (pin "P2") (pinfunction "P2_P2") (pintype "bidirectional"))
      (node (ref "C50") (pin "P2") (pinfunction "P2_P2") (pintype "bidirectional"))
      (node (ref "C51") (pin "P1") (pinfunction "P1_P1") (pintype "bidirectional"))
      (node (ref "C52") (pin "P2") (pinfunction "P2_P2") (pintype "bidirectional"))
      (node (ref "C53") (pin "P1") (pinfunction "P1_P1") (pintype "bidirectional"))
      (node (ref "C56") (pin "P2") (pinfunction "P2_P2") (pintype "bidirectional"))
      (node (ref "C57") (pin "P1") (pinfunction "P1_P1") (pintype "bidirectional"))
      (node (ref "C68") (pin "P1") (pinfunction "P1_P1") (pintype "bidirectional"))
      (node (ref "C69") (pin "P1") (pinfunction "P1_P1") (pintype "bidirectional"))
      (node (ref "C70") (pin "P2") (pinfunction "P2_P2") (pintype "bidirectional"))
      (node (ref "C71") (pin "P2") (pinfunction "P2_P2") (pintype "bidirectional"))
      (node (ref "C77") (pin "2") (pinfunction "P1_2") (pintype "bidirectional"))
      (node (ref "C78") (pin "P1") (pinfunction "P1_P1") (pintype "bidirectional"))
      (node (ref "C79") (pin "P1") (pinfunction "P1_P1") (pintype "bidirectional"))
      (node (ref "C80") (pin "2") (pinfunction "P1_2") (pintype "bidirectional"))
      (node (ref "F446") (pin "3") (pinfunction "3_3") (pintype "bidirectional"))
      (node (ref "L1@2") (pin "P1") (pinfunction "P1_P1") (pintype "bidirectional"))
      (node (ref "L2") (pin "2") (pinfunction "P2_2") (pintype "bidirectional"))
      (node (ref "R14") (pin "P1") (pinfunction "P1_P1") (pintype "bidirectional"))
      (node (ref "R15") (pin "P1") (pinfunction "P1_P1") (pintype "bidirectional"))
      (node (ref "R16") (pin "P1") (pinfunction "P1_P1") (pintype "bidirectional"))
      (node (ref "R19") (pin "P2") (pinfunction "P2_P2") (pintype "bidirectional"))
      (node (ref "R20") (pin "P1") (pinfunction "P1_P1") (pintype "bidirectional"))
      (node (ref "R22") (pin "P1") (pinfunction "P1_P1") (pintype "bidirectional"))
      (node (ref "R23") (pin "P1") (pinfunction "P1_P1") (pintype "bidirectional"))
      (node (ref "R32") (pin "P1") (pinfunction "P1_P1") (pintype "bidirectional"))
      (node (ref "R38") (pin "P1") (pinfunction "P1_P1") (pintype "bidirectional"))
      (node (ref "R50") (pin "P1") (pinfunction "P1_P1") (pintype "bidirectional"))
      (node (ref "U1") (pin "J12") (pinfunction "VDDIO_J12") (pintype "bidirectional"))
      (node (ref "U1") (pin "J18") (pinfunction "VBAT_J18") (pintype "bidirectional"))
      (node (ref "U2") (pin "1") (pinfunction "VBAT_1") (pintype "bidirectional"))
      (node (ref "U2") (pin "19") (pinfunction "VDD_19") (pintype "bidirectional"))
      (node (ref "U2") (pin "32") (pinfunction "VDD_32") (pintype "bidirectional"))
      (node (ref "U2") (pin "48") (pinfunction "VDD_48") (pintype "bidirectional"))
      (node (ref "U2") (pin "64") (pinfunction "VDDUSB_64") (pintype "bidirectional"))
      (node (ref "U3") (pin "7") (pinfunction "HOLD_7") (pintype "bidirectional"))
      (node (ref "U3") (pin "8") (pinfunction "VDD_8") (pintype "bidirectional"))
      (node (ref "X2") (pin "4") (pinfunction "VDD_4") (pintype "bidirectional"))
    )
    (net (code "2") (name "5V") (class "Default")
      (node (ref "C1@2") (pin "P2") (pinfunction "P2_P2") (pintype "bidirectional"))
      (node (ref "C62") (pin "2") (pinfunction "P1_2") (pintype "bidirectional"))
      (node (ref "C63") (pin "P1") (pinfunction "P1_P1") (pintype "bidirectional"))
      (node (ref "C64") (pin "P1") (pinfunction "P1_P1") (pintype "bidirectional"))
      (node (ref "C65") (pin "2") (pinfunction "P1_2") (pintype "bidirectional"))
      (node (ref "L1") (pin "2") (pinfunction "P2_2") (pintype "bidirectional"))
      (node (ref "LED1") (pin "5") (pinfunction "VCC_5") (pintype "bidirectional"))
      (node (ref "R41") (pin "P1") (pinfunction "P1_P1") (pintype "bidirectional"))
    )
    (net (code "3") (name "5V{slash}1.5D") (class "Default")
      (node (ref "C10@2") (pin "P2") (pinfunction "P2_P2") (pintype "bidirectional"))
      (node (ref "C11@2") (pin "P2") (pinfunction "P2_P2") (pintype "bidirectional"))
      (node (ref "C12@2") (pin "P2") (pinfunction "P2_P2") (pintype "bidirectional"))
      (node (ref "C13") (pin "P2") (pinfunction "P2_P2") (pintype "bidirectional"))
      (node (ref "C13@2") (pin "P2") (pinfunction "P2_P2") (pintype "bidirectional"))
      (node (ref "C15@2") (pin "P2") (pinfunction "P2_P2") (pintype "bidirectional"))
      (node (ref "C16@2") (pin "P2") (pinfunction "P2_P2") (pintype "bidirectional"))
      (node (ref "C17@2") (pin "P2") (pinfunction "P2_P2") (pintype "bidirectional"))
      (node (ref "C18@2") (pin "P2") (pinfunction "P2_P2") (pintype "bidirectional"))
      (node (ref "C19") (pin "P2") (pinfunction "P2_P2") (pintype "bidirectional"))
      (node (ref "C2") (pin "P2") (pinfunction "P2_P2") (pintype "bidirectional"))
      (node (ref "C20") (pin "P2") (pinfunction "P2_P2") (pintype "bidirectional"))
      (node (ref "C21") (pin "P2") (pinfunction "P2_P2") (pintype "bidirectional"))
      (node (ref "C22") (pin "P2") (pinfunction "P2_P2") (pintype "bidirectional"))
      (node (ref "C23") (pin "P2") (pinfunction "P2_P2") (pintype "bidirectional"))
      (node (ref "C24") (pin "P2") (pinfunction "P2_P2") (pintype "bidirectional"))
      (node (ref "C25") (pin "P2") (pinfunction "P2_P2") (pintype "bidirectional"))
      (node (ref "C26") (pin "P2") (pinfunction "P2_P2") (pintype "bidirectional"))
      (node (ref "C27") (pin "P2") (pinfunction "P2_P2") (pintype "bidirectional"))
      (node (ref "C28") (pin "P2") (pinfunction "P2_P2") (pintype "bidirectional"))
      (node (ref "C29") (pin "P2") (pinfunction "P2_P2") (pintype "bidirectional"))
      (node (ref "C2@2") (pin "P2") (pinfunction "P2_P2") (pintype "bidirectional"))
      (node (ref "C3") (pin "P2") (pinfunction "P2_P2") (pintype "bidirectional"))
      (node (ref "C30") (pin "P2") (pinfunction "P2_P2") (pintype "bidirectional"))
      (node (ref "C31") (pin "P2") (pinfunction "P2_P2") (pintype "bidirectional"))
      (node (ref "C32") (pin "P2") (pinfunction "P2_P2") (pintype "bidirectional"))
      (node (ref "C33") (pin "P2") (pinfunction "P2_P2") (pintype "bidirectional"))
      (node (ref "C34") (pin "P2") (pinfunction "P2_P2") (pintype "bidirectional"))
      (node (ref "C35") (pin "P2") (pinfunction "P2_P2") (pintype "bidirectional"))
      (node (ref "C3@2") (pin "P2") (pinfunction "P2_P2") (pintype "bidirectional"))
      (node (ref "C4") (pin "P2") (pinfunction "P2_P2") (pintype "bidirectional"))
      (node (ref "C4@2") (pin "P2") (pinfunction "P2_P2") (pintype "bidirectional"))
      (node (ref "C5") (pin "P2") (pinfunction "P2_P2") (pintype "bidirectional"))
      (node (ref "C5@2") (pin "P2") (pinfunction "P2_P2") (pintype "bidirectional"))
      (node (ref "C6") (pin "P2") (pinfunction "P2_P2") (pintype "bidirectional"))
      (node (ref "C6@2") (pin "P2") (pinfunction "P2_P2") (pintype "bidirectional"))
      (node (ref "C7") (pin "P2") (pinfunction "P2_P2") (pintype "bidirectional"))
      (node (ref "C7@2") (pin "P2") (pinfunction "P2_P2") (pintype "bidirectional"))
      (node (ref "C8") (pin "P2") (pinfunction "P2_P2") (pintype "bidirectional"))
      (node (ref "C8@2") (pin "P2") (pinfunction "P2_P2") (pintype "bidirectional"))
      (node (ref "C9@2") (pin "P2") (pinfunction "P2_P2") (pintype "bidirectional"))
      (node (ref "LED10") (pin "5") (pinfunction "VCC_5") (pintype "bidirectional"))
      (node (ref "LED11") (pin "5") (pinfunction "VCC_5") (pintype "bidirectional"))
      (node (ref "LED12") (pin "5") (pinfunction "VCC_5") (pintype "bidirectional"))
      (node (ref "LED13") (pin "5") (pinfunction "VCC_5") (pintype "bidirectional"))
      (node (ref "LED14") (pin "5") (pinfunction "VCC_5") (pintype "bidirectional"))
      (node (ref "LED15") (pin "5") (pinfunction "VCC_5") (pintype "bidirectional"))
      (node (ref "LED16") (pin "5") (pinfunction "VCC_5") (pintype "bidirectional"))
      (node (ref "LED17") (pin "5") (pinfunction "VCC_5") (pintype "bidirectional"))
      (node (ref "LED18") (pin "5") (pinfunction "VCC_5") (pintype "bidirectional"))
      (node (ref "LED19") (pin "5") (pinfunction "VCC_5") (pintype "bidirectional"))
      (node (ref "LED2") (pin "5") (pinfunction "VCC_5") (pintype "bidirectional"))
      (node (ref "LED20") (pin "5") (pinfunction "VCC_5") (pintype "bidirectional"))
      (node (ref "LED21") (pin "5") (pinfunction "VCC_5") (pintype "bidirectional"))
      (node (ref "LED22") (pin "5") (pinfunction "VCC_5") (pintype "bidirectional"))
      (node (ref "LED23") (pin "5") (pinfunction "VCC_5") (pintype "bidirectional"))
      (node (ref "LED24") (pin "5") (pinfunction "VCC_5") (pintype "bidirectional"))
      (node (ref "LED25") (pin "5") (pinfunction "VCC_5") (pintype "bidirectional"))
      (node (ref "LED26") (pin "5") (pinfunction "VCC_5") (pintype "bidirectional"))
      (node (ref "LED27") (pin "5") (pinfunction "VCC_5") (pintype "bidirectional"))
      (node (ref "LED28") (pin "5") (pinfunction "VCC_5") (pintype "bidirectional"))
      (node (ref "LED29") (pin "5") (pinfunction "VCC_5") (pintype "bidirectional"))
      (node (ref "LED3") (pin "5") (pinfunction "VCC_5") (pintype "bidirectional"))
      (node (ref "LED30") (pin "5") (pinfunction "VCC_5") (pintype "bidirectional"))
      (node (ref "LED31") (pin "5") (pinfunction "VCC_5") (pintype "bidirectional"))
      (node (ref "LED32") (pin "5") (pinfunction "VCC_5") (pintype "bidirectional"))
      (node (ref "LED33") (pin "5") (pinfunction "VCC_5") (pintype "bidirectional"))
      (node (ref "LED34") (pin "5") (pinfunction "VCC_5") (pintype "bidirectional"))
      (node (ref "LED35") (pin "5") (pinfunction "VCC_5") (pintype "bidirectional"))
      (node (ref "LED36") (pin "5") (pinfunction "VCC_5") (pintype "bidirectional"))
      (node (ref "LED37") (pin "5") (pinfunction "VCC_5") (pintype "bidirectional"))
      (node (ref "LED38") (pin "5") (pinfunction "VCC_5") (pintype "bidirectional"))
      (node (ref "LED39") (pin "5") (pinfunction "VCC_5") (pintype "bidirectional"))
      (node (ref "LED4") (pin "5") (pinfunction "VCC_5") (pintype "bidirectional"))
      (node (ref "LED40") (pin "5") (pinfunction "VCC_5") (pintype "bidirectional"))
      (node (ref "LED41") (pin "5") (pinfunction "VCC_5") (pintype "bidirectional"))
      (node (ref "LED42") (pin "5") (pinfunction "VCC_5") (pintype "bidirectional"))
      (node (ref "LED5") (pin "5") (pinfunction "VCC_5") (pintype "bidirectional"))
      (node (ref "LED6") (pin "5") (pinfunction "VCC_5") (pintype "bidirectional"))
      (node (ref "LED7") (pin "5") (pinfunction "VCC_5") (pintype "bidirectional"))
      (node (ref "LED8") (pin "5") (pinfunction "VCC_5") (pintype "bidirectional"))
      (node (ref "LED9") (pin "5") (pinfunction "VCC_5") (pintype "bidirectional"))
      (node (ref "Q1") (pin "E") (pinfunction "P3_E") (pintype "bidirectional"))
      (node (ref "Q3") (pin "E") (pinfunction "P3_E") (pintype "bidirectional"))
      (node (ref "R4@2") (pin "P2") (pinfunction "P2_P2") (pintype "bidirectional"))
      (node (ref "R9") (pin "P1") (pinfunction "P1_P1") (pintype "bidirectional"))
    )
    (net (code "4") (name "12V") (class "Default")
      (node (ref "C1") (pin "2") (pinfunction "P1_2") (pintype "bidirectional"))
      (node (ref "C59") (pin "P2") (pinfunction "P2_P2") (pintype "bidirectional"))
      (node (ref "C60") (pin "P2") (pinfunction "P2_P2") (pintype "bidirectional"))
      (node (ref "C74") (pin "P2") (pinfunction "P2_P2") (pintype "bidirectional"))
      (node (ref "C75") (pin "P2") (pinfunction "P2_P2") (pintype "bidirectional"))
      (node (ref "CON2") (pin "1") (pinfunction "1_1") (pintype "bidirectional"))
      (node (ref "U4") (pin "7") (pinfunction "VIN_7") (pintype "bidirectional"))
      (node (ref "U6") (pin "7") (pinfunction "VIN_7") (pintype "bidirectional"))
    )
    (net (code "5") (name "BTN0") (class "Default")
      (node (ref "C84") (pin "P2") (pinfunction "P2_P2") (pintype "bidirectional"))
      (node (ref "R14") (pin "P2") (pinfunction "P2_P2") (pintype "bidirectional"))
      (node (ref "SW1") (pin "1") (pinfunction "P2_1") (pintype "bidirectional"))
      (node (ref "SW1") (pin "2") (pinfunction "P2_2") (pintype "bidirectional"))
      (node (ref "U2") (pin "8") (pinfunction "PC0_8") (pintype "bidirectional"))
    )
    (net (code "6") (name "BTN1") (class "Default")
      (node (ref "C83") (pin "P2") (pinfunction "P2_P2") (pintype "bidirectional"))
      (node (ref "R15") (pin "P2") (pinfunction "P2_P2") (pintype "bidirectional"))
      (node (ref "SW2") (pin "1") (pinfunction "P2_1") (pintype "bidirectional"))
      (node (ref "SW2") (pin "2") (pinfunction "P2_2") (pintype "bidirectional"))
      (node (ref "U2") (pin "9") (pinfunction "PC1_9") (pintype "bidirectional"))
    )
    (net (code "7") (name "BTN2") (class "Default")
      (node (ref "C86") (pin "P2") (pinfunction "P2_P2") (pintype "bidirectional"))
      (node (ref "R16") (pin "P2") (pinfunction "P2_P2") (pintype "bidirectional"))
      (node (ref "SW3") (pin "1") (pinfunction "P2_1") (pintype "bidirectional"))
      (node (ref "SW3") (pin "2") (pinfunction "P2_2") (pintype "bidirectional"))
      (node (ref "U2") (pin "10") (pinfunction "PC2_10") (pintype "bidirectional"))
    )
    (net (code "8") (name "BTN3") (class "Default")
      (node (ref "C85") (pin "P2") (pinfunction "P2_P2") (pintype "bidirectional"))
      (node (ref "R23") (pin "P2") (pinfunction "P2_P2") (pintype "bidirectional"))
      (node (ref "SW4") (pin "1") (pinfunction "P2_1") (pintype "bidirectional"))
      (node (ref "SW4") (pin "2") (pinfunction "P2_2") (pintype "bidirectional"))
      (node (ref "U2") (pin "11") (pinfunction "PC3_11") (pintype "bidirectional"))
    )
    (net (code "9") (name "CHG-EN") (class "Default")
      (node (ref "R34") (pin "P1") (pinfunction "P1_P1") (pintype "bidirectional"))
      (node (ref "U4") (pin "5") (pinfunction "EN_5") (pintype "bidirectional"))
    )
    (net (code "10") (name "CI1") (class "Default")
      (node (ref "LED1") (pin "3") (pinfunction "CI_3") (pintype "bidirectional"))
      (node (ref "R3") (pin "P2") (pinfunction "P2_P2") (pintype "bidirectional"))
    )
    (net (code "11") (name "CO1") (class "Default")
      (node (ref "LED7") (pin "6") (pinfunction "CO_6") (pintype "bidirectional"))
      (node (ref "LED8") (pin "3") (pinfunction "CI_3") (pintype "bidirectional"))
    )
    (net (code "12") (name "CO2") (class "Default")
      (node (ref "LED14") (pin "6") (pinfunction "CO_6") (pintype "bidirectional"))
      (node (ref "LED15") (pin "3") (pinfunction "CI_3") (pintype "bidirectional"))
    )
    (net (code "13") (name "CO3") (class "Default")
      (node (ref "LED21") (pin "6") (pinfunction "CO_6") (pintype "bidirectional"))
      (node (ref "LED22") (pin "3") (pinfunction "CI_3") (pintype "bidirectional"))
    )
    (net (code "14") (name "CO4") (class "Default")
      (node (ref "LED28") (pin "6") (pinfunction "CO_6") (pintype "bidirectional"))
      (node (ref "LED29") (pin "3") (pinfunction "CI_3") (pintype "bidirectional"))
    )
    (net (code "15") (name "CO5") (class "Default")
      (node (ref "LED35") (pin "6") (pinfunction "CO_6") (pintype "bidirectional"))
      (node (ref "LED36") (pin "3") (pinfunction "CI_3") (pintype "bidirectional"))
    )
    (net (code "16") (name "CO6") (class "Default")
      (node (ref "LED42") (pin "6") (pinfunction "CO_6") (pintype "bidirectional"))
    )
    (net (code "17") (name "DI1") (class "Default")
      (node (ref "LED1") (pin "1") (pinfunction "DI_1") (pintype "bidirectional"))
      (node (ref "R5") (pin "P1") (pinfunction "P1_P1") (pintype "bidirectional"))
    )
    (net (code "18") (name "DO1") (class "Default")
      (node (ref "LED7") (pin "2") (pinfunction "DO_2") (pintype "bidirectional"))
      (node (ref "LED8") (pin "1") (pinfunction "DI_1") (pintype "bidirectional"))
    )
    (net (code "19") (name "DO2") (class "Default")
      (node (ref "LED14") (pin "2") (pinfunction "DO_2") (pintype "bidirectional"))
      (node (ref "LED15") (pin "1") (pinfunction "DI_1") (pintype "bidirectional"))
    )
    (net (code "20") (name "DO3") (class "Default")
      (node (ref "LED21") (pin "2") (pinfunction "DO_2") (pintype "bidirectional"))
      (node (ref "LED22") (pin "1") (pinfunction "DI_1") (pintype "bidirectional"))
    )
    (net (code "21") (name "DO4") (class "Default")
      (node (ref "LED28") (pin "2") (pinfunction "DO_2") (pintype "bidirectional"))
      (node (ref "LED29") (pin "1") (pinfunction "DI_1") (pintype "bidirectional"))
    )
    (net (code "22") (name "DO5") (class "Default")
      (node (ref "LED35") (pin "2") (pinfunction "DO_2") (pintype "bidirectional"))
      (node (ref "LED36") (pin "1") (pinfunction "DI_1") (pintype "bidirectional"))
    )
    (net (code "23") (name "DO6") (class "Default")
      (node (ref "LED42") (pin "2") (pinfunction "DO_2") (pintype "bidirectional"))
    )
    (net (code "24") (name "F446-DRX") (class "Default")
      (node (ref "F446") (pin "10") (pinfunction "10_10") (pintype "bidirectional"))
      (node (ref "U2") (pin "59") (pinfunction "PB7_59") (pintype "bidirectional"))
    )
    (net (code "25") (name "F446-DTX") (class "Default")
      (node (ref "F446") (pin "9") (pinfunction "9_9") (pintype "bidirectional"))
      (node (ref "U2") (pin "58") (pinfunction "PB6_58") (pintype "bidirectional"))
    )
    (net (code "26") (name "F446-NRST") (class "Default")
      (node (ref "C48") (pin "P2") (pinfunction "P2_P2") (pintype "bidirectional"))
      (node (ref "F446") (pin "12") (pinfunction "12_12") (pintype "bidirectional"))
      (node (ref "R19") (pin "P1") (pinfunction "P1_P1") (pintype "bidirectional"))
      (node (ref "U2") (pin "7") (pinfunction "NRST_7") (pintype "bidirectional"))
    )
    (net (code "27") (name "F446-SWDCLK") (class "Default")
      (node (ref "F446") (pin "6") (pinfunction "6_6") (pintype "bidirectional"))
      (node (ref "U2") (pin "49") (pinfunction "PA14_49") (pintype "bidirectional"))
    )
    (net (code "28") (name "F446-SWDIO") (class "Default")
      (node (ref "F446") (pin "4") (pinfunction "4_4") (pintype "bidirectional"))
      (node (ref "U2") (pin "46") (pinfunction "PA13_46") (pintype "bidirectional"))
    )
    (net (code "29") (name "FLASH-CS") (class "Default")
      (node (ref "U2") (pin "33") (pinfunction "PB12_33") (pintype "bidirectional"))
      (node (ref "U3") (pin "1") (pinfunction "CE_1") (pintype "bidirectional"))
    )
    (net (code "30") (name "FLASH-MISO") (class "Default")
      (node (ref "U2") (pin "35") (pinfunction "PB14_35") (pintype "bidirectional"))
      (node (ref "U3") (pin "2") (pinfunction "MISO_2") (pintype "bidirectional"))
    )
    (net (code "31") (name "FLASH-MOSI") (class "Default")
      (node (ref "U2") (pin "36") (pinfunction "PB15_36") (pintype "bidirectional"))
      (node (ref "U3") (pin "5") (pinfunction "MOSI_5") (pintype "bidirectional"))
    )
    (net (code "32") (name "FLASH-SCK") (class "Default")
      (node (ref "U2") (pin "34") (pinfunction "PB13_34") (pintype "bidirectional"))
      (node (ref "U3") (pin "6") (pinfunction "SCK_6") (pintype "bidirectional"))
    )
    (net (code "33") (name "GND") (class "Default")
      (node (ref "C1") (pin "1") (pinfunction "P2_1") (pintype "bidirectional"))
      (node (ref "C43") (pin "P1") (pinfunction "P1_P1") (pintype "bidirectional"))
      (node (ref "C44") (pin "P1") (pinfunction "P1_P1") (pintype "bidirectional"))
      (node (ref "C45") (pin "P1") (pinfunction "P1_P1") (pintype "bidirectional"))
      (node (ref "C46") (pin "P1") (pinfunction "P1_P1") (pintype "bidirectional"))
      (node (ref "C47") (pin "P1") (pinfunction "P1_P1") (pintype "bidirectional"))
      (node (ref "C48") (pin "P1") (pinfunction "P1_P1") (pintype "bidirectional"))
      (node (ref "C49") (pin "P1") (pinfunction "P1_P1") (pintype "bidirectional"))
      (node (ref "C50") (pin "P1") (pinfunction "P1_P1") (pintype "bidirectional"))
      (node (ref "C51") (pin "P2") (pinfunction "P2_P2") (pintype "bidirectional"))
      (node (ref "C52") (pin "P1") (pinfunction "P1_P1") (pintype "bidirectional"))
      (node (ref "C53") (pin "P2") (pinfunction "P2_P2") (pintype "bidirectional"))
      (node (ref "C54") (pin "P2") (pinfunction "P2_P2") (pintype "bidirectional"))
      (node (ref "C55") (pin "P2") (pinfunction "P2_P2") (pintype "bidirectional"))
      (node (ref "C56") (pin "P1") (pinfunction "P1_P1") (pintype "bidirectional"))
      (node (ref "C57") (pin "P2") (pinfunction "P2_P2") (pintype "bidirectional"))
      (node (ref "C59") (pin "P1") (pinfunction "P1_P1") (pintype "bidirectional"))
      (node (ref "C60") (pin "P1") (pinfunction "P1_P1") (pintype "bidirectional"))
      (node (ref "C62") (pin "1") (pinfunction "P2_1") (pintype "bidirectional"))
      (node (ref "C63") (pin "P2") (pinfunction "P2_P2") (pintype "bidirectional"))
      (node (ref "C64") (pin "P2") (pinfunction "P2_P2") (pintype "bidirectional"))
      (node (ref "C65") (pin "1") (pinfunction "P2_1") (pintype "bidirectional"))
      (node (ref "C66") (pin "P2") (pinfunction "P2_P2") (pintype "bidirectional"))
      (node (ref "C67") (pin "P2") (pinfunction "P2_P2") (pintype "bidirectional"))
      (node (ref "C68") (pin "P2") (pinfunction "P2_P2") (pintype "bidirectional"))
      (node (ref "C69") (pin "P2") (pinfunction "P2_P2") (pintype "bidirectional"))
      (node (ref "C70") (pin "P1") (pinfunction "P1_P1") (pintype "bidirectional"))
      (node (ref "C71") (pin "P1") (pinfunction "P1_P1") (pintype "bidirectional"))
      (node (ref "C72") (pin "P2") (pinfunction "P2_P2") (pintype "bidirectional"))
      (node (ref "C73") (pin "P2") (pinfunction "P2_P2") (pintype "bidirectional"))
      (node (ref "C74") (pin "P1") (pinfunction "P1_P1") (pintype "bidirectional"))
      (node (ref "C75") (pin "P1") (pinfunction "P1_P1") (pintype "bidirectional"))
      (node (ref "C77") (pin "1") (pinfunction "P2_1") (pintype "bidirectional"))
      (node (ref "C78") (pin "P2") (pinfunction "P2_P2") (pintype "bidirectional"))
      (node (ref "C79") (pin "P2") (pinfunction "P2_P2") (pintype "bidirectional"))
      (node (ref "C80") (pin "1") (pinfunction "P2_1") (pintype "bidirectional"))
      (node (ref "C81") (pin "P2") (pinfunction "P2_P2") (pintype "bidirectional"))
      (node (ref "C82") (pin "P2") (pinfunction "P2_P2") (pintype "bidirectional"))
      (node (ref "CON2") (pin "2") (pinfunction "2_2") (pintype "bidirectional"))
      (node (ref "CON2") (pin "3") (pinfunction "3_3") (pintype "bidirectional"))
      (node (ref "D1") (pin "1") (pinfunction "P1_1") (pintype "bidirectional"))
      (node (ref "D2") (pin "1") (pinfunction "P1_1") (pintype "bidirectional"))
      (node (ref "F446") (pin "11") (pinfunction "11_11") (pintype "bidirectional"))
      (node (ref "F446") (pin "5") (pinfunction "5_5") (pintype "bidirectional"))
      (node (ref "F446") (pin "7") (pinfunction "7_7") (pintype "bidirectional"))
      (node (ref "R17") (pin "P2") (pinfunction "P2_P2") (pintype "bidirectional"))
      (node (ref "R21") (pin "P1") (pinfunction "P1_P1") (pintype "bidirectional"))
      (node (ref "R25") (pin "P1") (pinfunction "P1_P1") (pintype "bidirectional"))
      (node (ref "R26") (pin "P1") (pinfunction "P1_P1") (pintype "bidirectional"))
      (node (ref "R4") (pin "P1") (pinfunction "P1_P1") (pintype "bidirectional"))
      (node (ref "R43") (pin "P1") (pinfunction "P1_P1") (pintype "bidirectional"))
      (node (ref "R44") (pin "P2") (pinfunction "P2_P2") (pintype "bidirectional"))
      (node (ref "R46") (pin "P2") (pinfunction "P2_P2") (pintype "bidirectional"))
      (node (ref "R53") (pin "P2") (pinfunction "P2_P2") (pintype "bidirectional"))
      (node (ref "U1") (pin "J1") (pinfunction "GND_J1") (pintype "bidirectional"))
      (node (ref "U1") (pin "J13") (pinfunction "GND_J13") (pintype "bidirectional"))
      (node (ref "U1") (pin "J21") (pinfunction "GND_J21") (pintype "bidirectional"))
      (node (ref "U1") (pin "J28") (pinfunction "GND_J28") (pintype "bidirectional"))
      (node (ref "U1") (pin "J36") (pinfunction "GND_J36") (pintype "bidirectional"))
      (node (ref "U2") (pin "12") (pinfunction "VSSA_12") (pintype "bidirectional"))
      (node (ref "U2") (pin "18") (pinfunction "VSS_18") (pintype "bidirectional"))
      (node (ref "U2") (pin "31") (pinfunction "VSS_31") (pintype "bidirectional"))
      (node (ref "U2") (pin "47") (pinfunction "VSS_47") (pintype "bidirectional"))
      (node (ref "U2") (pin "63") (pinfunction "VSS_63") (pintype "bidirectional"))
      (node (ref "U3") (pin "3") (pinfunction "WP_3") (pintype "bidirectional"))
      (node (ref "U3") (pin "4") (pinfunction "VSS_4") (pintype "bidirectional"))
      (node (ref "U4") (pin "6") (pinfunction "GND_6") (pintype "bidirectional"))
      (node (ref "U6") (pin "6") (pinfunction "GND_6") (pintype "bidirectional"))
      (node (ref "X1") (pin "1") (pinfunction "GND_1") (pintype "bidirectional"))
      (node (ref "X1") (pin "4") (pinfunction "GND_4") (pintype "bidirectional"))
      (node (ref "X2") (pin "2") (pinfunction "GND_2") (pintype "bidirectional"))
    )
    (net (code "34") (name "GND{slash}1.7C") (class "Default")
      (node (ref "Q2") (pin "E") (pinfunction "P3_E") (pintype "bidirectional"))
      (node (ref "Q4") (pin "E") (pinfunction "P3_E") (pintype "bidirectional"))
      (node (ref "Q5") (pin "3") (pinfunction "P2_3") (pintype "bidirectional"))
      (node (ref "R13") (pin "P1") (pinfunction "P1_P1") (pintype "bidirectional"))
      (node (ref "R2") (pin "P2") (pinfunction "P2_P2") (pintype "bidirectional"))
      (node (ref "R5@1") (pin "P1") (pinfunction "P1_P1") (pintype "bidirectional"))
      (node (ref "R5@2") (pin "P1") (pinfunction "P1_P1") (pintype "bidirectional"))
      (node (ref "R8") (pin "P2") (pinfunction "P2_P2") (pintype "bidirectional"))
    )
    (net (code "35") (name "GND{slash}2.5A") (class "Default")
      (node (ref "C83") (pin "P1") (pinfunction "P1_P1") (pintype "bidirectional"))
      (node (ref "C84") (pin "P1") (pinfunction "P1_P1") (pintype "bidirectional"))
      (node (ref "C85") (pin "P1") (pinfunction "P1_P1") (pintype "bidirectional"))
      (node (ref "C86") (pin "P1") (pinfunction "P1_P1") (pintype "bidirectional"))
      (node (ref "SW1") (pin "3") (pinfunction "P1_3") (pintype "bidirectional"))
      (node (ref "SW1") (pin "4") (pinfunction "P1_4") (pintype "bidirectional"))
      (node (ref "SW2") (pin "3") (pinfunction "P1_3") (pintype "bidirectional"))
      (node (ref "SW2") (pin "4") (pinfunction "P1_4") (pintype "bidirectional"))
      (node (ref "SW3") (pin "3") (pinfunction "P1_3") (pintype "bidirectional"))
      (node (ref "SW3") (pin "4") (pinfunction "P1_4") (pintype "bidirectional"))
      (node (ref "SW4") (pin "3") (pinfunction "P1_3") (pintype "bidirectional"))
      (node (ref "SW4") (pin "4") (pinfunction "P1_4") (pintype "bidirectional"))
    )
    (net (code "36") (name "LED-GND") (class "Default")
      (node (ref "C10@2") (pin "P1") (pinfunction "P1_P1") (pintype "bidirectional"))
      (node (ref "C11@2") (pin "P1") (pinfunction "P1_P1") (pintype "bidirectional"))
      (node (ref "C12@2") (pin "P1") (pinfunction "P1_P1") (pintype "bidirectional"))
      (node (ref "C13") (pin "P1") (pinfunction "P1_P1") (pintype "bidirectional"))
      (node (ref "C13@2") (pin "P1") (pinfunction "P1_P1") (pintype "bidirectional"))
      (node (ref "C15@2") (pin "P1") (pinfunction "P1_P1") (pintype "bidirectional"))
      (node (ref "C16@2") (pin "P1") (pinfunction "P1_P1") (pintype "bidirectional"))
      (node (ref "C17@2") (pin "P1") (pinfunction "P1_P1") (pintype "bidirectional"))
      (node (ref "C18@2") (pin "P1") (pinfunction "P1_P1") (pintype "bidirectional"))
      (node (ref "C19") (pin "P1") (pinfunction "P1_P1") (pintype "bidirectional"))
      (node (ref "C1@2") (pin "P1") (pinfunction "P1_P1") (pintype "bidirectional"))
      (node (ref "C2") (pin "P1") (pinfunction "P1_P1") (pintype "bidirectional"))
      (node (ref "C20") (pin "P1") (pinfunction "P1_P1") (pintype "bidirectional"))
      (node (ref "C21") (pin "P1") (pinfunction "P1_P1") (pintype "bidirectional"))
      (node (ref "C22") (pin "P1") (pinfunction "P1_P1") (pintype "bidirectional"))
      (node (ref "C23") (pin "P1") (pinfunction "P1_P1") (pintype "bidirectional"))
      (node (ref "C24") (pin "P1") (pinfunction "P1_P1") (pintype "bidirectional"))
      (node (ref "C25") (pin "P1") (pinfunction "P1_P1") (pintype "bidirectional"))
      (node (ref "C26") (pin "P1") (pinfunction "P1_P1") (pintype "bidirectional"))
      (node (ref "C27") (pin "P1") (pinfunction "P1_P1") (pintype "bidirectional"))
      (node (ref "C28") (pin "P1") (pinfunction "P1_P1") (pintype "bidirectional"))
      (node (ref "C29") (pin "P1") (pinfunction "P1_P1") (pintype "bidirectional"))
      (node (ref "C2@2") (pin "P1") (pinfunction "P1_P1") (pintype "bidirectional"))
      (node (ref "C3") (pin "P1") (pinfunction "P1_P1") (pintype "bidirectional"))
      (node (ref "C30") (pin "P1") (pinfunction "P1_P1") (pintype "bidirectional"))
      (node (ref "C31") (pin "P1") (pinfunction "P1_P1") (pintype "bidirectional"))
      (node (ref "C32") (pin "P1") (pinfunction "P1_P1") (pintype "bidirectional"))
      (node (ref "C33") (pin "P1") (pinfunction "P1_P1") (pintype "bidirectional"))
      (node (ref "C34") (pin "P1") (pinfunction "P1_P1") (pintype "bidirectional"))
      (node (ref "C35") (pin "P1") (pinfunction "P1_P1") (pintype "bidirectional"))
      (node (ref "C3@2") (pin "P1") (pinfunction "P1_P1") (pintype "bidirectional"))
      (node (ref "C4") (pin "P1") (pinfunction "P1_P1") (pintype "bidirectional"))
      (node (ref "C4@2") (pin "P1") (pinfunction "P1_P1") (pintype "bidirectional"))
      (node (ref "C5") (pin "P1") (pinfunction "P1_P1") (pintype "bidirectional"))
      (node (ref "C5@2") (pin "P1") (pinfunction "P1_P1") (pintype "bidirectional"))
      (node (ref "C6") (pin "P1") (pinfunction "P1_P1") (pintype "bidirectional"))
      (node (ref "C6@2") (pin "P1") (pinfunction "P1_P1") (pintype "bidirectional"))
      (node (ref "C7") (pin "P1") (pinfunction "P1_P1") (pintype "bidirectional"))
      (node (ref "C7@2") (pin "P1") (pinfunction "P1_P1") (pintype "bidirectional"))
      (node (ref "C8") (pin "P1") (pinfunction "P1_P1") (pintype "bidirectional"))
      (node (ref "C8@2") (pin "P1") (pinfunction "P1_P1") (pintype "bidirectional"))
      (node (ref "C9@2") (pin "P1") (pinfunction "P1_P1") (pintype "bidirectional"))
      (node (ref "LED1") (pin "4") (pinfunction "GND_4") (pintype "bidirectional"))
      (node (ref "LED10") (pin "4") (pinfunction "GND_4") (pintype "bidirectional"))
      (node (ref "LED11") (pin "4") (pinfunction "GND_4") (pintype "bidirectional"))
      (node (ref "LED12") (pin "4") (pinfunction "GND_4") (pintype "bidirectional"))
      (node (ref "LED13") (pin "4") (pinfunction "GND_4") (pintype "bidirectional"))
      (node (ref "LED14") (pin "4") (pinfunction "GND_4") (pintype "bidirectional"))
      (node (ref "LED15") (pin "4") (pinfunction "GND_4") (pintype "bidirectional"))
      (node (ref "LED16") (pin "4") (pinfunction "GND_4") (pintype "bidirectional"))
      (node (ref "LED17") (pin "4") (pinfunction "GND_4") (pintype "bidirectional"))
      (node (ref "LED18") (pin "4") (pinfunction "GND_4") (pintype "bidirectional"))
      (node (ref "LED19") (pin "4") (pinfunction "GND_4") (pintype "bidirectional"))
      (node (ref "LED2") (pin "4") (pinfunction "GND_4") (pintype "bidirectional"))
      (node (ref "LED20") (pin "4") (pinfunction "GND_4") (pintype "bidirectional"))
      (node (ref "LED21") (pin "4") (pinfunction "GND_4") (pintype "bidirectional"))
      (node (ref "LED22") (pin "4") (pinfunction "GND_4") (pintype "bidirectional"))
      (node (ref "LED23") (pin "4") (pinfunction "GND_4") (pintype "bidirectional"))
      (node (ref "LED24") (pin "4") (pinfunction "GND_4") (pintype "bidirectional"))
      (node (ref "LED25") (pin "4") (pinfunction "GND_4") (pintype "bidirectional"))
      (node (ref "LED26") (pin "4") (pinfunction "GND_4") (pintype "bidirectional"))
      (node (ref "LED27") (pin "4") (pinfunction "GND_4") (pintype "bidirectional"))
      (node (ref "LED28") (pin "4") (pinfunction "GND_4") (pintype "bidirectional"))
      (node (ref "LED29") (pin "4") (pinfunction "GND_4") (pintype "bidirectional"))
      (node (ref "LED3") (pin "4") (pinfunction "GND_4") (pintype "bidirectional"))
      (node (ref "LED30") (pin "4") (pinfunction "GND_4") (pintype "bidirectional"))
      (node (ref "LED31") (pin "4") (pinfunction "GND_4") (pintype "bidirectional"))
      (node (ref "LED32") (pin "4") (pinfunction "GND_4") (pintype "bidirectional"))
      (node (ref "LED33") (pin "4") (pinfunction "GND_4") (pintype "bidirectional"))
      (node (ref "LED34") (pin "4") (pinfunction "GND_4") (pintype "bidirectional"))
      (node (ref "LED35") (pin "4") (pinfunction "GND_4") (pintype "bidirectional"))
      (node (ref "LED36") (pin "4") (pinfunction "GND_4") (pintype "bidirectional"))
      (node (ref "LED37") (pin "4") (pinfunction "GND_4") (pintype "bidirectional"))
      (node (ref "LED38") (pin "4") (pinfunction "GND_4") (pintype "bidirectional"))
      (node (ref "LED39") (pin "4") (pinfunction "GND_4") (pintype "bidirectional"))
      (node (ref "LED4") (pin "4") (pinfunction "GND_4") (pintype "bidirectional"))
      (node (ref "LED40") (pin "4") (pinfunction "GND_4") (pintype "bidirectional"))
      (node (ref "LED41") (pin "4") (pinfunction "GND_4") (pintype "bidirectional"))
      (node (ref "LED42") (pin "4") (pinfunction "GND_4") (pintype "bidirectional"))
      (node (ref "LED5") (pin "4") (pinfunction "GND_4") (pintype "bidirectional"))
      (node (ref "LED6") (pin "4") (pinfunction "GND_4") (pintype "bidirectional"))
      (node (ref "LED7") (pin "4") (pinfunction "GND_4") (pintype "bidirectional"))
      (node (ref "LED8") (pin "4") (pinfunction "GND_4") (pintype "bidirectional"))
      (node (ref "LED9") (pin "4") (pinfunction "GND_4") (pintype "bidirectional"))
      (node (ref "Q5") (pin "1") (pinfunction "P1_1") (pintype "bidirectional"))
    )
    (net (code "37") (name "LED-PWR-EN") (class "Default")
      (node (ref "Q5") (pin "2") (pinfunction "P3_2") (pintype "bidirectional"))
      (node (ref "R13") (pin "P2") (pinfunction "P2_P2") (pintype "bidirectional"))
      (node (ref "U2") (pin "55") (pinfunction "PB3_55") (pintype "bidirectional"))
    )
    (net (code "38") (name "LEDS-DATA") (class "Default")
      (node (ref "Q4") (pin "B") (pinfunction "P2_B") (pintype "bidirectional"))
      (node (ref "R5@1") (pin "P2") (pinfunction "P2_P2") (pintype "bidirectional"))
      (node (ref "R7") (pin "P2") (pinfunction "P2_P2") (pintype "bidirectional"))
      (node (ref "U2") (pin "56") (pinfunction "PB4_56") (pintype "bidirectional"))
    )
    (net (code "39") (name "LEDS-SCK") (class "Default")
      (node (ref "Q2") (pin "B") (pinfunction "P2_B") (pintype "bidirectional"))
      (node (ref "R1") (pin "P1") (pinfunction "P1_P1") (pintype "bidirectional"))
      (node (ref "R5@2") (pin "P2") (pinfunction "P2_P2") (pintype "bidirectional"))
      (node (ref "U2") (pin "57") (pinfunction "PB5_57") (pintype "bidirectional"))
    )
    (net (code "40") (name "NTC") (class "Default")
      (node (ref "R32") (pin "P2") (pinfunction "P2_P2") (pintype "bidirectional"))
      (node (ref "R4") (pin "P2") (pinfunction "P22_P2") (pintype "bidirectional"))
      (node (ref "U2") (pin "14") (pinfunction "PA0_14") (pintype "bidirectional"))
    )
    (net (code "41") (name "Net-(C61-PadP2)") (class "Default")
      (node (ref "C61") (pin "P2") (pinfunction "P2_P2") (pintype "bidirectional"))
      (node (ref "R39") (pin "P2") (pinfunction "P2_P2") (pintype "bidirectional"))
    )
    (net (code "42") (name "Net-(C66-PadP1)") (class "Default")
      (node (ref "C66") (pin "P1") (pinfunction "P1_P1") (pintype "bidirectional"))
      (node (ref "R37") (pin "P1") (pinfunction "P1_P1") (pintype "bidirectional"))
    )
    (net (code "43") (name "Net-(C67-PadP1)") (class "Default")
      (node (ref "C67") (pin "P1") (pinfunction "P1_P1") (pintype "bidirectional"))
      (node (ref "R50") (pin "P2") (pinfunction "P2_P2") (pintype "bidirectional"))
    )
    (net (code "44") (name "Net-(C76-PadP1)") (class "Default")
      (node (ref "C76") (pin "P1") (pinfunction "P1_P1") (pintype "bidirectional"))
      (node (ref "R35") (pin "P2") (pinfunction "P2_P2") (pintype "bidirectional"))
    )
    (net (code "45") (name "Net-(C76-PadP2)") (class "Default")
      (node (ref "C76") (pin "P2") (pinfunction "P2_P2") (pintype "bidirectional"))
      (node (ref "R36") (pin "P2") (pinfunction "P2_P2") (pintype "bidirectional"))
    )
    (net (code "46") (name "Net-(C81-PadP1)") (class "Default")
      (node (ref "C81") (pin "P1") (pinfunction "P1_P1") (pintype "bidirectional"))
      (node (ref "R35") (pin "P1") (pinfunction "P1_P1") (pintype "bidirectional"))
    )
    (net (code "47") (name "Net-(C82-PadP1)") (class "Default")
      (node (ref "C82") (pin "P1") (pinfunction "P1_P1") (pintype "bidirectional"))
      (node (ref "R43") (pin "P2") (pinfunction "P2_P2") (pintype "bidirectional"))
    )
    (net (code "48") (name "Net-(D1-P2)") (class "Default")
      (node (ref "D1") (pin "2") (pinfunction "P2_2") (pintype "bidirectional"))
      (node (ref "L2") (pin "1") (pinfunction "P1_1") (pintype "bidirectional"))
      (node (ref "U6") (pin "8") (pinfunction "SW_8") (pintype "bidirectional"))
    )
    (net (code "49") (name "Net-(D2-P2)") (class "Default")
      (node (ref "C61") (pin "P1") (pinfunction "P1_P1") (pintype "bidirectional"))
      (node (ref "D2") (pin "2") (pinfunction "P2_2") (pintype "bidirectional"))
      (node (ref "R37") (pin "P2") (pinfunction "P2_P2") (pintype "bidirectional"))
    )
    (net (code "50") (name "Net-(L1-P1)") (class "Default")
      (node (ref "L1") (pin "1") (pinfunction "P1_1") (pintype "bidirectional"))
      (node (ref "U4") (pin "8") (pinfunction "SW_8") (pintype "bidirectional"))
    )
    (net (code "51") (name "Net-(LED1-CO)") (class "Default")
      (node (ref "LED1") (pin "6") (pinfunction "CO_6") (pintype "bidirectional"))
      (node (ref "LED2") (pin "3") (pinfunction "CI_3") (pintype "bidirectional"))
    )
    (net (code "52") (name "Net-(LED1-DO)") (class "Default")
      (node (ref "LED1") (pin "2") (pinfunction "DO_2") (pintype "bidirectional"))
      (node (ref "LED2") (pin "1") (pinfunction "DI_1") (pintype "bidirectional"))
    )
    (net (code "53") (name "Net-(LED2-CO)") (class "Default")
      (node (ref "LED2") (pin "6") (pinfunction "CO_6") (pintype "bidirectional"))
      (node (ref "LED3") (pin "3") (pinfunction "CI_3") (pintype "bidirectional"))
    )
    (net (code "54") (name "Net-(LED2-DO)") (class "Default")
      (node (ref "LED2") (pin "2") (pinfunction "DO_2") (pintype "bidirectional"))
      (node (ref "LED3") (pin "1") (pinfunction "DI_1") (pintype "bidirectional"))
    )
    (net (code "55") (name "Net-(LED3-CO)") (class "Default")
      (node (ref "LED3") (pin "6") (pinfunction "CO_6") (pintype "bidirectional"))
      (node (ref "LED4") (pin "3") (pinfunction "CI_3") (pintype "bidirectional"))
    )
    (net (code "56") (name "Net-(LED3-DO)") (class "Default")
      (node (ref "LED3") (pin "2") (pinfunction "DO_2") (pintype "bidirectional"))
      (node (ref "LED4") (pin "1") (pinfunction "DI_1") (pintype "bidirectional"))
    )
    (net (code "57") (name "Net-(LED4-CO)") (class "Default")
      (node (ref "LED4") (pin "6") (pinfunction "CO_6") (pintype "bidirectional"))
      (node (ref "LED5") (pin "3") (pinfunction "CI_3") (pintype "bidirectional"))
    )
    (net (code "58") (name "Net-(LED4-DO)") (class "Default")
      (node (ref "LED4") (pin "2") (pinfunction "DO_2") (pintype "bidirectional"))
      (node (ref "LED5") (pin "1") (pinfunction "DI_1") (pintype "bidirectional"))
    )
    (net (code "59") (name "Net-(LED5-CO)") (class "Default")
      (node (ref "LED5") (pin "6") (pinfunction "CO_6") (pintype "bidirectional"))
      (node (ref "LED6") (pin "3") (pinfunction "CI_3") (pintype "bidirectional"))
    )
    (net (code "60") (name "Net-(LED5-DO)") (class "Default")
      (node (ref "LED5") (pin "2") (pinfunction "DO_2") (pintype "bidirectional"))
      (node (ref "LED6") (pin "1") (pinfunction "DI_1") (pintype "bidirectional"))
    )
    (net (code "61") (name "Net-(LED6-CO)") (class "Default")
      (node (ref "LED6") (pin "6") (pinfunction "CO_6") (pintype "bidirectional"))
      (node (ref "LED7") (pin "3") (pinfunction "CI_3") (pintype "bidirectional"))
    )
    (net (code "62") (name "Net-(LED6-DO)") (class "Default")
      (node (ref "LED6") (pin "2") (pinfunction "DO_2") (pintype "bidirectional"))
      (node (ref "LED7") (pin "1") (pinfunction "DI_1") (pintype "bidirectional"))
    )
    (net (code "63") (name "Net-(LED8-CO)") (class "Default")
      (node (ref "LED8") (pin "6") (pinfunction "CO_6") (pintype "bidirectional"))
      (node (ref "LED9") (pin "3") (pinfunction "CI_3") (pintype "bidirectional"))
    )
    (net (code "64") (name "Net-(LED8-DO)") (class "Default")
      (node (ref "LED8") (pin "2") (pinfunction "DO_2") (pintype "bidirectional"))
      (node (ref "LED9") (pin "1") (pinfunction "DI_1") (pintype "bidirectional"))
    )
    (net (code "65") (name "Net-(LED10-CI)") (class "Default")
      (node (ref "LED10") (pin "3") (pinfunction "CI_3") (pintype "bidirectional"))
      (node (ref "LED9") (pin "6") (pinfunction "CO_6") (pintype "bidirectional"))
    )
    (net (code "66") (name "Net-(LED10-CO)") (class "Default")
      (node (ref "LED10") (pin "6") (pinfunction "CO_6") (pintype "bidirectional"))
      (node (ref "LED11") (pin "3") (pinfunction "CI_3") (pintype "bidirectional"))
    )
    (net (code "67") (name "Net-(LED10-DI)") (class "Default")
      (node (ref "LED10") (pin "1") (pinfunction "DI_1") (pintype "bidirectional"))
      (node (ref "LED9") (pin "2") (pinfunction "DO_2") (pintype "bidirectional"))
    )
    (net (code "68") (name "Net-(LED10-DO)") (class "Default")
      (node (ref "LED10") (pin "2") (pinfunction "DO_2") (pintype "bidirectional"))
      (node (ref "LED11") (pin "1") (pinfunction "DI_1") (pintype "bidirectional"))
    )
    (net (code "69") (name "Net-(LED11-CO)") (class "Default")
      (node (ref "LED11") (pin "6") (pinfunction "CO_6") (pintype "bidirectional"))
      (node (ref "LED12") (pin "3") (pinfunction "CI_3") (pintype "bidirectional"))
    )
    (net (code "70") (name "Net-(LED11-DO)") (class "Default")
      (node (ref "LED11") (pin "2") (pinfunction "DO_2") (pintype "bidirectional"))
      (node (ref "LED12") (pin "1") (pinfunction "DI_1") (pintype "bidirectional"))
    )
    (net (code "71") (name "Net-(LED12-CO)") (class "Default")
      (node (ref "LED12") (pin "6") (pinfunction "CO_6") (pintype "bidirectional"))
      (node (ref "LED13") (pin "3") (pinfunction "CI_3") (pintype "bidirectional"))
    )
    (net (code "72") (name "Net-(LED12-DO)") (class "Default")
      (node (ref "LED12") (pin "2") (pinfunction "DO_2") (pintype "bidirectional"))
      (node (ref "LED13") (pin "1") (pinfunction "DI_1") (pintype "bidirectional"))
    )
    (net (code "73") (name "Net-(LED13-CO)") (class "Default")
      (node (ref "LED13") (pin "6") (pinfunction "CO_6") (pintype "bidirectional"))
      (node (ref "LED14") (pin "3") (pinfunction "CI_3") (pintype "bidirectional"))
    )
    (net (code "74") (name "Net-(LED13-DO)") (class "Default")
      (node (ref "LED13") (pin "2") (pinfunction "DO_2") (pintype "bidirectional"))
      (node (ref "LED14") (pin "1") (pinfunction "DI_1") (pintype "bidirectional"))
    )
    (net (code "75") (name "Net-(LED15-CO)") (class "Default")
      (node (ref "LED15") (pin "6") (pinfunction "CO_6") (pintype "bidirectional"))
      (node (ref "LED16") (pin "3") (pinfunction "CI_3") (pintype "bidirectional"))
    )
    (net (code "76") (name "Net-(LED15-DO)") (class "Default")
      (node (ref "LED15") (pin "2") (pinfunction "DO_2") (pintype "bidirectional"))
      (node (ref "LED16") (pin "1") (pinfunction "DI_1") (pintype "bidirectional"))
    )
    (net (code "77") (name "Net-(LED16-CO)") (class "Default")
      (node (ref "LED16") (pin "6") (pinfunction "CO_6") (pintype "bidirectional"))
      (node (ref "LED17") (pin "3") (pinfunction "CI_3") (pintype "bidirectional"))
    )
    (net (code "78") (name "Net-(LED16-DO)") (class "Default")
      (node (ref "LED16") (pin "2") (pinfunction "DO_2") (pintype "bidirectional"))
      (node (ref "LED17") (pin "1") (pinfunction "DI_1") (pintype "bidirectional"))
    )
    (net (code "79") (name "Net-(LED17-CO)") (class "Default")
      (node (ref "LED17") (pin "6") (pinfunction "CO_6") (pintype "bidirectional"))
      (node (ref "LED18") (pin "3") (pinfunction "CI_3") (pintype "bidirectional"))
    )
    (net (code "80") (name "Net-(LED17-DO)") (class "Default")
      (node (ref "LED17") (pin "2") (pinfunction "DO_2") (pintype "bidirectional"))
      (node (ref "LED18") (pin "1") (pinfunction "DI_1") (pintype "bidirectional"))
    )
    (net (code "81") (name "Net-(LED18-CO)") (class "Default")
      (node (ref "LED18") (pin "6") (pinfunction "CO_6") (pintype "bidirectional"))
      (node (ref "LED19") (pin "3") (pinfunction "CI_3") (pintype "bidirectional"))
    )
    (net (code "82") (name "Net-(LED18-DO)") (class "Default")
      (node (ref "LED18") (pin "2") (pinfunction "DO_2") (pintype "bidirectional"))
      (node (ref "LED19") (pin "1") (pinfunction "DI_1") (pintype "bidirectional"))
    )
    (net (code "83") (name "Net-(LED19-CO)") (class "Default")
      (node (ref "LED19") (pin "6") (pinfunction "CO_6") (pintype "bidirectional"))
      (node (ref "LED20") (pin "3") (pinfunction "CI_3") (pintype "bidirectional"))
    )
    (net (code "84") (name "Net-(LED19-DO)") (class "Default")
      (node (ref "LED19") (pin "2") (pinfunction "DO_2") (pintype "bidirectional"))
      (node (ref "LED20") (pin "1") (pinfunction "DI_1") (pintype "bidirectional"))
    )
    (net (code "85") (name "Net-(LED20-CO)") (class "Default")
      (node (ref "LED20") (pin "6") (pinfunction "CO_6") (pintype "bidirectional"))
      (node (ref "LED21") (pin "3") (pinfunction "CI_3") (pintype "bidirectional"))
    )
    (net (code "86") (name "Net-(LED20-DO)") (class "Default")
      (node (ref "LED20") (pin "2") (pinfunction "DO_2") (pintype "bidirectional"))
      (node (ref "LED21") (pin "1") (pinfunction "DI_1") (pintype "bidirectional"))
    )
    (net (code "87") (name "Net-(LED22-CO)") (class "Default")
      (node (ref "LED22") (pin "6") (pinfunction "CO_6") (pintype "bidirectional"))
      (node (ref "LED23") (pin "3") (pinfunction "CI_3") (pintype "bidirectional"))
    )
    (net (code "88") (name "Net-(LED22-DO)") (class "Default")
      (node (ref "LED22") (pin "2") (pinfunction "DO_2") (pintype "bidirectional"))
      (node (ref "LED23") (pin "1") (pinfunction "DI_1") (pintype "bidirectional"))
    )
    (net (code "89") (name "Net-(LED23-CO)") (class "Default")
      (node (ref "LED23") (pin "6") (pinfunction "CO_6") (pintype "bidirectional"))
      (node (ref "LED24") (pin "3") (pinfunction "CI_3") (pintype "bidirectional"))
    )
    (net (code "90") (name "Net-(LED23-DO)") (class "Default")
      (node (ref "LED23") (pin "2") (pinfunction "DO_2") (pintype "bidirectional"))
      (node (ref "LED24") (pin "1") (pinfunction "DI_1") (pintype "bidirectional"))
    )
    (net (code "91") (name "Net-(LED24-CO)") (class "Default")
      (node (ref "LED24") (pin "6") (pinfunction "CO_6") (pintype "bidirectional"))
      (node (ref "LED25") (pin "3") (pinfunction "CI_3") (pintype "bidirectional"))
    )
    (net (code "92") (name "Net-(LED24-DO)") (class "Default")
      (node (ref "LED24") (pin "2") (pinfunction "DO_2") (pintype "bidirectional"))
      (node (ref "LED25") (pin "1") (pinfunction "DI_1") (pintype "bidirectional"))
    )
    (net (code "93") (name "Net-(LED25-CO)") (class "Default")
      (node (ref "LED25") (pin "6") (pinfunction "CO_6") (pintype "bidirectional"))
      (node (ref "LED26") (pin "3") (pinfunction "CI_3") (pintype "bidirectional"))
    )
    (net (code "94") (name "Net-(LED25-DO)") (class "Default")
      (node (ref "LED25") (pin "2") (pinfunction "DO_2") (pintype "bidirectional"))
      (node (ref "LED26") (pin "1") (pinfunction "DI_1") (pintype "bidirectional"))
    )
    (net (code "95") (name "Net-(LED26-CO)") (class "Default")
      (node (ref "LED26") (pin "6") (pinfunction "CO_6") (pintype "bidirectional"))
      (node (ref "LED27") (pin "3") (pinfunction "CI_3") (pintype "bidirectional"))
    )
    (net (code "96") (name "Net-(LED26-DO)") (class "Default")
      (node (ref "LED26") (pin "2") (pinfunction "DO_2") (pintype "bidirectional"))
      (node (ref "LED27") (pin "1") (pinfunction "DI_1") (pintype "bidirectional"))
    )
    (net (code "97") (name "Net-(LED27-CO)") (class "Default")
      (node (ref "LED27") (pin "6") (pinfunction "CO_6") (pintype "bidirectional"))
      (node (ref "LED28") (pin "3") (pinfunction "CI_3") (pintype "bidirectional"))
    )
    (net (code "98") (name "Net-(LED27-DO)") (class "Default")
      (node (ref "LED27") (pin "2") (pinfunction "DO_2") (pintype "bidirectional"))
      (node (ref "LED28") (pin "1") (pinfunction "DI_1") (pintype "bidirectional"))
    )
    (net (code "99") (name "Net-(LED29-CO)") (class "Default")
      (node (ref "LED29") (pin "6") (pinfunction "CO_6") (pintype "bidirectional"))
      (node (ref "LED30") (pin "3") (pinfunction "CI_3") (pintype "bidirectional"))
    )
    (net (code "100") (name "Net-(LED29-DO)") (class "Default")
      (node (ref "LED29") (pin "2") (pinfunction "DO_2") (pintype "bidirectional"))
      (node (ref "LED30") (pin "1") (pinfunction "DI_1") (pintype "bidirectional"))
    )
    (net (code "101") (name "Net-(LED30-CO)") (class "Default")
      (node (ref "LED30") (pin "6") (pinfunction "CO_6") (pintype "bidirectional"))
      (node (ref "LED31") (pin "3") (pinfunction "CI_3") (pintype "bidirectional"))
    )
    (net (code "102") (name "Net-(LED30-DO)") (class "Default")
      (node (ref "LED30") (pin "2") (pinfunction "DO_2") (pintype "bidirectional"))
      (node (ref "LED31") (pin "1") (pinfunction "DI_1") (pintype "bidirectional"))
    )
    (net (code "103") (name "Net-(LED31-CO)") (class "Default")
      (node (ref "LED31") (pin "6") (pinfunction "CO_6") (pintype "bidirectional"))
      (node (ref "LED32") (pin "3") (pinfunction "CI_3") (pintype "bidirectional"))
    )
    (net (code "104") (name "Net-(LED31-DO)") (class "Default")
      (node (ref "LED31") (pin "2") (pinfunction "DO_2") (pintype "bidirectional"))
      (node (ref "LED32") (pin "1") (pinfunction "DI_1") (pintype "bidirectional"))
    )
    (net (code "105") (name "Net-(LED32-CO)") (class "Default")
      (node (ref "LED32") (pin "6") (pinfunction "CO_6") (pintype "bidirectional"))
      (node (ref "LED33") (pin "3") (pinfunction "CI_3") (pintype "bidirectional"))
    )
    (net (code "106") (name "Net-(LED32-DO)") (class "Default")
      (node (ref "LED32") (pin "2") (pinfunction "DO_2") (pintype "bidirectional"))
      (node (ref "LED33") (pin "1") (pinfunction "DI_1") (pintype "bidirectional"))
    )
    (net (code "107") (name "Net-(LED33-CO)") (class "Default")
      (node (ref "LED33") (pin "6") (pinfunction "CO_6") (pintype "bidirectional"))
      (node (ref "LED34") (pin "3") (pinfunction "CI_3") (pintype "bidirectional"))
    )
    (net (code "108") (name "Net-(LED33-DO)") (class "Default")
      (node (ref "LED33") (pin "2") (pinfunction "DO_2") (pintype "bidirectional"))
      (node (ref "LED34") (pin "1") (pinfunction "DI_1") (pintype "bidirectional"))
    )
    (net (code "109") (name "Net-(LED34-CO)") (class "Default")
      (node (ref "LED34") (pin "6") (pinfunction "CO_6") (pintype "bidirectional"))
      (node (ref "LED35") (pin "3") (pinfunction "CI_3") (pintype "bidirectional"))
    )
    (net (code "110") (name "Net-(LED34-DO)") (class "Default")
      (node (ref "LED34") (pin "2") (pinfunction "DO_2") (pintype "bidirectional"))
      (node (ref "LED35") (pin "1") (pinfunction "DI_1") (pintype "bidirectional"))
    )
    (net (code "111") (name "Net-(LED36-CO)") (class "Default")
      (node (ref "LED36") (pin "6") (pinfunction "CO_6") (pintype "bidirectional"))
      (node (ref "LED37") (pin "3") (pinfunction "CI_3") (pintype "bidirectional"))
    )
    (net (code "112") (name "Net-(LED36-DO)") (class "Default")
      (node (ref "LED36") (pin "2") (pinfunction "DO_2") (pintype "bidirectional"))
      (node (ref "LED37") (pin "1") (pinfunction "DI_1") (pintype "bidirectional"))
    )
    (net (code "113") (name "Net-(LED37-CO)") (class "Default")
      (node (ref "LED37") (pin "6") (pinfunction "CO_6") (pintype "bidirectional"))
      (node (ref "LED38") (pin "3") (pinfunction "CI_3") (pintype "bidirectional"))
    )
    (net (code "114") (name "Net-(LED37-DO)") (class "Default")
      (node (ref "LED37") (pin "2") (pinfunction "DO_2") (pintype "bidirectional"))
      (node (ref "LED38") (pin "1") (pinfunction "DI_1") (pintype "bidirectional"))
    )
    (net (code "115") (name "Net-(LED38-CO)") (class "Default")
      (node (ref "LED38") (pin "6") (pinfunction "CO_6") (pintype "bidirectional"))
      (node (ref "LED39") (pin "3") (pinfunction "CI_3") (pintype "bidirectional"))
    )
    (net (code "116") (name "Net-(LED38-DO)") (class "Default")
      (node (ref "LED38") (pin "2") (pinfunction "DO_2") (pintype "bidirectional"))
      (node (ref "LED39") (pin "1") (pinfunction "DI_1") (pintype "bidirectional"))
    )
    (net (code "117") (name "Net-(LED39-CO)") (class "Default")
      (node (ref "LED39") (pin "6") (pinfunction "CO_6") (pintype "bidirectional"))
      (node (ref "LED40") (pin "3") (pinfunction "CI_3") (pintype "bidirectional"))
    )
    (net (code "118") (name "Net-(LED39-DO)") (class "Default")
      (node (ref "LED39") (pin "2") (pinfunction "DO_2") (pintype "bidirectional"))
      (node (ref "LED40") (pin "1") (pinfunction "DI_1") (pintype "bidirectional"))
    )
    (net (code "119") (name "Net-(LED40-CO)") (class "Default")
      (node (ref "LED40") (pin "6") (pinfunction "CO_6") (pintype "bidirectional"))
      (node (ref "LED41") (pin "3") (pinfunction "CI_3") (pintype "bidirectional"))
    )
    (net (code "120") (name "Net-(LED40-DO)") (class "Default")
      (node (ref "LED40") (pin "2") (pinfunction "DO_2") (pintype "bidirectional"))
      (node (ref "LED41") (pin "1") (pinfunction "DI_1") (pintype "bidirectional"))
    )
    (net (code "121") (name "Net-(LED41-CO)") (class "Default")
      (node (ref "LED41") (pin "6") (pinfunction "CO_6") (pintype "bidirectional"))
      (node (ref "LED42") (pin "3") (pinfunction "CI_3") (pintype "bidirectional"))
    )
    (net (code "122") (name "Net-(LED41-DO)") (class "Default")
      (node (ref "LED41") (pin "2") (pinfunction "DO_2") (pintype "bidirectional"))
      (node (ref "LED42") (pin "1") (pinfunction "DI_1") (pintype "bidirectional"))
    )
    (net (code "123") (name "Net-(Q1-P1-PadC)") (class "Default")
      (node (ref "Q1") (pin "C") (pinfunction "P1_C") (pintype "bidirectional"))
      (node (ref "Q1") (pin "C@2") (pinfunction "P1_C@2") (pintype "bidirectional"))
      (node (ref "R2") (pin "P1") (pinfunction "P1_P1") (pintype "bidirectional"))
      (node (ref "R3") (pin "P1") (pinfunction "P1_P1") (pintype "bidirectional"))
    )
    (net (code "124") (name "Net-(Q1-P2)") (class "Default")
      (node (ref "Q1") (pin "B") (pinfunction "P2_B") (pintype "bidirectional"))
      (node (ref "Q2") (pin "C") (pinfunction "P1_C") (pintype "bidirectional"))
      (node (ref "Q2") (pin "C@2") (pinfunction "P1_C@2") (pintype "bidirectional"))
      (node (ref "R4@2") (pin "P1") (pinfunction "P1_P1") (pintype "bidirectional"))
      (node (ref "R6") (pin "P2") (pinfunction "P2_P2") (pintype "bidirectional"))
    )
    (net (code "125") (name "Net-(Q3-P1-PadC)") (class "Default")
      (node (ref "Q3") (pin "C") (pinfunction "P1_C") (pintype "bidirectional"))
      (node (ref "Q3") (pin "C@2") (pinfunction "P1_C@2") (pintype "bidirectional"))
      (node (ref "R5") (pin "P2") (pinfunction "P2_P2") (pintype "bidirectional"))
      (node (ref "R8") (pin "P1") (pinfunction "P1_P1") (pintype "bidirectional"))
    )
    (net (code "126") (name "Net-(Q3-P2)") (class "Default")
      (node (ref "Q3") (pin "B") (pinfunction "P2_B") (pintype "bidirectional"))
      (node (ref "Q4") (pin "C") (pinfunction "P1_C") (pintype "bidirectional"))
      (node (ref "Q4") (pin "C@2") (pinfunction "P1_C@2") (pintype "bidirectional"))
      (node (ref "R12") (pin "P2") (pinfunction "P2_P2") (pintype "bidirectional"))
      (node (ref "R9") (pin "P2") (pinfunction "P2_P2") (pintype "bidirectional"))
    )
    (net (code "127") (name "Net-(R1-PadP2)") (class "Default")
      (node (ref "R1") (pin "P2") (pinfunction "P2_P2") (pintype "bidirectional"))
      (node (ref "R6") (pin "P1") (pinfunction "P1_P1") (pintype "bidirectional"))
    )
    (net (code "128") (name "Net-(R12-PadP1)") (class "Default")
      (node (ref "R12") (pin "P1") (pinfunction "P1_P1") (pintype "bidirectional"))
      (node (ref "R7") (pin "P1") (pinfunction "P1_P1") (pintype "bidirectional"))
    )
    (net (code "129") (name "Net-(R42-PadP2)") (class "Default")
      (node (ref "R42") (pin "P2") (pinfunction "P2_P2") (pintype "bidirectional"))
      (node (ref "R44") (pin "P1") (pinfunction "P1_P1") (pintype "bidirectional"))
    )
    (net (code "130") (name "Net-(R45-PadP2)") (class "Default")
      (node (ref "R45") (pin "P2") (pinfunction "P2_P2") (pintype "bidirectional"))
      (node (ref "R53") (pin "P1") (pinfunction "P1_P1") (pintype "bidirectional"))
    )
    (net (code "131") (name "Net-(U1-RTC-CLK)") (class "Default")
      (node (ref "U1") (pin "J20") (pinfunction "RTC-CLK_J20") (pintype "bidirectional"))
      (node (ref "X2") (pin "1") (pinfunction "OUT_1") (pintype "bidirectional"))
    )
    (net (code "132") (name "Net-(U1-SPI-CFG)") (class "Default")
      (node (ref "R22") (pin "P2") (pinfunction "P2_P2") (pintype "bidirectional"))
      (node (ref "U1") (pin "J2") (pinfunction "SPI-CFG_J2") (pintype "bidirectional"))
    )
    (net (code "133") (name "Net-(U2-BOOT0)") (class "Default")
      (node (ref "R17") (pin "P1") (pinfunction "P1_P1") (pintype "bidirectional"))
      (node (ref "U2") (pin "60") (pinfunction "BOOT0_60") (pintype "bidirectional"))
    )
    (net (code "134") (name "Net-(U2-PB10)") (class "Default")
      (node (ref "R34") (pin "P2") (pinfunction "P2_P2") (pintype "bidirectional"))
      (node (ref "U2") (pin "29") (pinfunction "PB10_29") (pintype "bidirectional"))
    )
    (net (code "135") (name "Net-(U2-PH0)") (class "Default")
      (node (ref "C54") (pin "P1") (pinfunction "P1_P1") (pintype "bidirectional"))
      (node (ref "U2") (pin "5") (pinfunction "PH0_5") (pintype "bidirectional"))
      (node (ref "X1") (pin "3") (pinfunction "P3_3") (pintype "bidirectional"))
    )
    (net (code "136") (name "Net-(U2-PH1)") (class "Default")
      (node (ref "R18") (pin "P1") (pinfunction "P1_P1") (pintype "bidirectional"))
      (node (ref "U2") (pin "6") (pinfunction "PH1_6") (pintype "bidirectional"))
    )
    (net (code "137") (name "Net-(U2-VCAP)") (class "Default")
      (node (ref "C46") (pin "P2") (pinfunction "P2_P2") (pintype "bidirectional"))
      (node (ref "U2") (pin "30") (pinfunction "VCAP_30") (pintype "bidirectional"))
    )
    (net (code "138") (name "Net-(U2-VDDA)") (class "Default")
      (node (ref "C49") (pin "P2") (pinfunction "P2_P2") (pintype "bidirectional"))
      (node (ref "L1@2") (pin "P2") (pinfunction "P2_P2") (pintype "bidirectional"))
      (node (ref "U2") (pin "13") (pinfunction "VDDA_13") (pintype "bidirectional"))
    )
    (net (code "139") (name "Net-(U4-BOOT)") (class "Default")
      (node (ref "R39") (pin "P1") (pinfunction "P1_P1") (pintype "bidirectional"))
      (node (ref "U4") (pin "1") (pinfunction "BOOT_1") (pintype "bidirectional"))
    )
    (net (code "140") (name "Net-(U4-FB)") (class "Default")
      (node (ref "R41") (pin "P2") (pinfunction "P2_P2") (pintype "bidirectional"))
      (node (ref "R45") (pin "P1") (pinfunction "P1_P1") (pintype "bidirectional"))
      (node (ref "U4") (pin "4") (pinfunction "FB_4") (pintype "bidirectional"))
    )
    (net (code "141") (name "Net-(U6-BOOT)") (class "Default")
      (node (ref "R36") (pin "P1") (pinfunction "P1_P1") (pintype "bidirectional"))
      (node (ref "U6") (pin "1") (pinfunction "BOOT_1") (pintype "bidirectional"))
    )
    (net (code "142") (name "Net-(U6-EN)") (class "Default")
      (node (ref "R46") (pin "P1") (pinfunction "P1_P1") (pintype "bidirectional"))
      (node (ref "U6") (pin "5") (pinfunction "EN_5") (pintype "bidirectional"))
    )
    (net (code "143") (name "Net-(U6-FB)") (class "Default")
      (node (ref "R38") (pin "P2") (pinfunction "P2_P2") (pintype "bidirectional"))
      (node (ref "R42") (pin "P1") (pinfunction "P1_P1") (pintype "bidirectional"))
      (node (ref "U6") (pin "4") (pinfunction "FB_4") (pintype "bidirectional"))
    )
    (net (code "144") (name "Net-(ULD1-P2)") (class "Default")
      (node (ref "R25") (pin "P2") (pinfunction "P2_P2") (pintype "bidirectional"))
      (node (ref "ULD1") (pin "1") (pinfunction "P2_1") (pintype "bidirectional"))
    )
    (net (code "145") (name "Net-(ULD2-P2)") (class "Default")
      (node (ref "R26") (pin "P2") (pinfunction "P2_P2") (pintype "bidirectional"))
      (node (ref "ULD2") (pin "1") (pinfunction "P2_1") (pintype "bidirectional"))
    )
    (net (code "146") (name "Net-(X1-P2)") (class "Default")
      (node (ref "C55") (pin "P1") (pinfunction "P1_P1") (pintype "bidirectional"))
      (node (ref "R18") (pin "P2") (pinfunction "P2_P2") (pintype "bidirectional"))
      (node (ref "X1") (pin "2") (pinfunction "P2_2") (pintype "bidirectional"))
    )
    (net (code "147") (name "Net-(X2-OE)") (class "Default")
      (node (ref "C72") (pin "P1") (pinfunction "P1_P1") (pintype "bidirectional"))
      (node (ref "X2") (pin "3") (pinfunction "OE_3") (pintype "bidirectional"))
    )
    (net (code "148") (name "ULD0") (class "Default")
      (node (ref "U2") (pin "61") (pinfunction "PB8_61") (pintype "bidirectional"))
      (node (ref "ULD2") (pin "2") (pinfunction "P1_2") (pintype "bidirectional"))
    )
    (net (code "149") (name "ULD1") (class "Default")
      (node (ref "U2") (pin "62") (pinfunction "PB9_62") (pintype "bidirectional"))
      (node (ref "ULD1") (pin "2") (pinfunction "P1_2") (pintype "bidirectional"))
    )
    (net (code "150") (name "WIFI-CS") (class "Default")
      (node (ref "U1") (pin "J25") (pinfunction "SPI-SSN_J25") (pintype "bidirectional"))
      (node (ref "U2") (pin "20") (pinfunction "PA4_20") (pintype "bidirectional"))
    )
    (net (code "151") (name "WIFI-EN") (class "Default")
      (node (ref "R21") (pin "P2") (pinfunction "P2_P2") (pintype "bidirectional"))
      (node (ref "U1") (pin "J19") (pinfunction "CHIP-EN_J19") (pintype "bidirectional"))
      (node (ref "U2") (pin "24") (pinfunction "PC4_24") (pintype "bidirectional"))
    )
    (net (code "152") (name "WIFI-IRQ") (class "Default")
      (node (ref "U1") (pin "J33") (pinfunction "IRQN_J33") (pintype "bidirectional"))
      (node (ref "U2") (pin "26") (pinfunction "PB0_26") (pintype "bidirectional"))
    )
    (net (code "153") (name "WIFI-MISO") (class "Default")
      (node (ref "U1") (pin "J24") (pinfunction "SPI-MISO_J24") (pintype "bidirectional"))
      (node (ref "U2") (pin "22") (pinfunction "PA6_22") (pintype "bidirectional"))
    )
    (net (code "154") (name "WIFI-MOSI") (class "Default")
      (node (ref "U1") (pin "J26") (pinfunction "SPI-MOSI_J26") (pintype "bidirectional"))
      (node (ref "U2") (pin "23") (pinfunction "PA7_23") (pintype "bidirectional"))
    )
    (net (code "155") (name "WIFI-RESET") (class "Default")
      (node (ref "C73") (pin "P1") (pinfunction "P1_P1") (pintype "bidirectional"))
      (node (ref "R20") (pin "P2") (pinfunction "P2_P2") (pintype "bidirectional"))
      (node (ref "U1") (pin "J7") (pinfunction "RESETN_J7") (pintype "bidirectional"))
      (node (ref "U2") (pin "25") (pinfunction "PC5_25") (pintype "bidirectional"))
    )
    (net (code "156") (name "WIFI-SCK") (class "Default")
      (node (ref "U1") (pin "J23") (pinfunction "SPI-SCK_J23") (pintype "bidirectional"))
      (node (ref "U2") (pin "21") (pinfunction "PA5_21") (pintype "bidirectional"))
    )
    (net (code "157") (name "unconnected-(F446-Pad1)") (class "Default")
      (node (ref "F446") (pin "1") (pinfunction "1_1") (pintype "bidirectional"))
    )
    (net (code "158") (name "unconnected-(F446-Pad2)") (class "Default")
      (node (ref "F446") (pin "2") (pinfunction "2_2") (pintype "bidirectional"))
    )
    (net (code "159") (name "unconnected-(F446-Pad8)") (class "Default")
      (node (ref "F446") (pin "8") (pinfunction "8_8") (pintype "bidirectional"))
    )
    (net (code "160") (name "unconnected-(F446-Pad13)") (class "Default")
      (node (ref "F446") (pin "13") (pinfunction "13_13") (pintype "bidirectional"))
    )
    (net (code "161") (name "unconnected-(F446-Pad14)") (class "Default")
      (node (ref "F446") (pin "14") (pinfunction "14_14") (pintype "bidirectional"))
    )
    (net (code "162") (name "unconnected-(U1-BT-RXD-PadJ9)") (class "Default")
      (node (ref "U1") (pin "J9") (pinfunction "BT-RXD_J9") (pintype "bidirectional"))
    )
    (net (code "163") (name "unconnected-(U1-BT-TXD-PadJ8)") (class "Default")
      (node (ref "U1") (pin "J8") (pinfunction "BT-TXD_J8") (pintype "bidirectional"))
    )
    (net (code "164") (name "unconnected-(U1-GPIO3-PadJ14)") (class "Default")
      (node (ref "U1") (pin "J14") (pinfunction "GPIO3_J14") (pintype "bidirectional"))
    )
    (net (code "165") (name "unconnected-(U1-GPIO4-PadJ15)") (class "Default")
      (node (ref "U1") (pin "J15") (pinfunction "GPIO4_J15") (pintype "bidirectional"))
    )
    (net (code "166") (name "unconnected-(U1-GPIO7-PadJ27)") (class "Default")
      (node (ref "U1") (pin "J27") (pinfunction "GPIO7_J27") (pintype "bidirectional"))
    )
    (net (code "167") (name "unconnected-(U1-GPIO8-PadJ22)") (class "Default")
      (node (ref "U1") (pin "J22") (pinfunction "GPIO8_J22") (pintype "bidirectional"))
    )
    (net (code "168") (name "unconnected-(U1-GPIO17-PadJ29)") (class "Default")
      (node (ref "U1") (pin "J29") (pinfunction "GPIO17_J29") (pintype "bidirectional"))
    )
    (net (code "169") (name "unconnected-(U1-GPIO18-PadJ30)") (class "Default")
      (node (ref "U1") (pin "J30") (pinfunction "GPIO18_J30") (pintype "bidirectional"))
    )
    (net (code "170") (name "unconnected-(U1-GPIO19-PadJ31)") (class "Default")
      (node (ref "U1") (pin "J31") (pinfunction "GPIO19_J31") (pintype "bidirectional"))
    )
    (net (code "171") (name "unconnected-(U1-GPIO20-PadJ32)") (class "Default")
      (node (ref "U1") (pin "J32") (pinfunction "GPIO20_J32") (pintype "bidirectional"))
    )
    (net (code "172") (name "unconnected-(U1-I2C-SCLM-PadJ34)") (class "Default")
      (node (ref "U1") (pin "J34") (pinfunction "I2C-SCLM_J34") (pintype "bidirectional"))
    )
    (net (code "173") (name "unconnected-(U1-I2C-SCLS-PadJ11)") (class "Default")
      (node (ref "U1") (pin "J11") (pinfunction "I2C-SCLS_J11") (pintype "bidirectional"))
    )
    (net (code "174") (name "unconnected-(U1-I2C-SDAM-PadJ35)") (class "Default")
      (node (ref "U1") (pin "J35") (pinfunction "I2C-SDAM_J35") (pintype "bidirectional"))
    )
    (net (code "175") (name "unconnected-(U1-I2C-SDAS-PadJ10)") (class "Default")
      (node (ref "U1") (pin "J10") (pinfunction "I2C-SDAS_J10") (pintype "bidirectional"))
    )
    (net (code "176") (name "unconnected-(U1-NC-PadJ3)") (class "Default")
      (node (ref "U1") (pin "J3") (pinfunction "NC_J3") (pintype "bidirectional"))
    )
    (net (code "177") (name "unconnected-(U1-NC-PadJ4)") (class "Default")
      (node (ref "U1") (pin "J4") (pinfunction "NC_J4") (pintype "bidirectional"))
    )
    (net (code "178") (name "unconnected-(U1-NC-PadJ5)") (class "Default")
      (node (ref "U1") (pin "J5") (pinfunction "NC_J5") (pintype "bidirectional"))
    )
    (net (code "179") (name "unconnected-(U1-NC-PadJ6)") (class "Default")
      (node (ref "U1") (pin "J6") (pinfunction "NC_J6") (pintype "bidirectional"))
    )
    (net (code "180") (name "unconnected-(U1-UART-RXD-PadJ17)") (class "Default")
      (node (ref "U1") (pin "J17") (pinfunction "UART-RXD_J17") (pintype "bidirectional"))
    )
    (net (code "181") (name "unconnected-(U1-UART-TXD-PadJ16)") (class "Default")
      (node (ref "U1") (pin "J16") (pinfunction "UART-TXD_J16") (pintype "bidirectional"))
    )
    (net (code "182") (name "unconnected-(U2-PA1-Pad15)") (class "Default")
      (node (ref "U2") (pin "15") (pinfunction "PA1_15") (pintype "bidirectional"))
    )
    (net (code "183") (name "unconnected-(U2-PA2-Pad16)") (class "Default")
      (node (ref "U2") (pin "16") (pinfunction "PA2_16") (pintype "bidirectional"))
    )
    (net (code "184") (name "unconnected-(U2-PA3-Pad17)") (class "Default")
      (node (ref "U2") (pin "17") (pinfunction "PA3_17") (pintype "bidirectional"))
    )
    (net (code "185") (name "unconnected-(U2-PA8-Pad41)") (class "Default")
      (node (ref "U2") (pin "41") (pinfunction "PA8_41") (pintype "bidirectional"))
    )
    (net (code "186") (name "unconnected-(U2-PA9-Pad42)") (class "Default")
      (node (ref "U2") (pin "42") (pinfunction "PA9_42") (pintype "bidirectional"))
    )
    (net (code "187") (name "unconnected-(U2-PA10-Pad43)") (class "Default")
      (node (ref "U2") (pin "43") (pinfunction "PA10_43") (pintype "bidirectional"))
    )
    (net (code "188") (name "unconnected-(U2-PA11-Pad44)") (class "Default")
      (node (ref "U2") (pin "44") (pinfunction "PA11_44") (pintype "bidirectional"))
    )
    (net (code "189") (name "unconnected-(U2-PA12-Pad45)") (class "Default")
      (node (ref "U2") (pin "45") (pinfunction "PA12_45") (pintype "bidirectional"))
    )
    (net (code "190") (name "unconnected-(U2-PA15-Pad50)") (class "Default")
      (node (ref "U2") (pin "50") (pinfunction "PA15_50") (pintype "bidirectional"))
    )
    (net (code "191") (name "unconnected-(U2-PB1-Pad27)") (class "Default")
      (node (ref "U2") (pin "27") (pinfunction "PB1_27") (pintype "bidirectional"))
    )
    (net (code "192") (name "unconnected-(U2-PB2-Pad28)") (class "Default")
      (node (ref "U2") (pin "28") (pinfunction "PB2_28") (pintype "bidirectional"))
    )
    (net (code "193") (name "unconnected-(U2-PC6-Pad37)") (class "Default")
      (node (ref "U2") (pin "37") (pinfunction "PC6_37") (pintype "bidirectional"))
    )
    (net (code "194") (name "unconnected-(U2-PC7-Pad38)") (class "Default")
      (node (ref "U2") (pin "38") (pinfunction "PC7_38") (pintype "bidirectional"))
    )
    (net (code "195") (name "unconnected-(U2-PC8-Pad39)") (class "Default")
      (node (ref "U2") (pin "39") (pinfunction "PC8_39") (pintype "bidirectional"))
    )
    (net (code "196") (name "unconnected-(U2-PC9-Pad40)") (class "Default")
      (node (ref "U2") (pin "40") (pinfunction "PC9_40") (pintype "bidirectional"))
    )
    (net (code "197") (name "unconnected-(U2-PC10-Pad51)") (class "Default")
      (node (ref "U2") (pin "51") (pinfunction "PC10_51") (pintype "bidirectional"))
    )
    (net (code "198") (name "unconnected-(U2-PC11-Pad52)") (class "Default")
      (node (ref "U2") (pin "52") (pinfunction "PC11_52") (pintype "bidirectional"))
    )
    (net (code "199") (name "unconnected-(U2-PC12-Pad53)") (class "Default")
      (node (ref "U2") (pin "53") (pinfunction "PC12_53") (pintype "bidirectional"))
    )
    (net (code "200") (name "unconnected-(U2-PC13-Pad2)") (class "Default")
      (node (ref "U2") (pin "2") (pinfunction "PC13_2") (pintype "bidirectional"))
    )
    (net (code "201") (name "unconnected-(U2-PC14-Pad3)") (class "Default")
      (node (ref "U2") (pin "3") (pinfunction "PC14_3") (pintype "bidirectional"))
    )
    (net (code "202") (name "unconnected-(U2-PC15-Pad4)") (class "Default")
      (node (ref "U2") (pin "4") (pinfunction "PC15_4") (pintype "bidirectional"))
    )
    (net (code "203") (name "unconnected-(U2-PD2-Pad54)") (class "Default")
      (node (ref "U2") (pin "54") (pinfunction "PD2_54") (pintype "bidirectional"))
    )
    (net (code "204") (name "unconnected-(U4-NC-Pad2)") (class "Default")
      (node (ref "U4") (pin "2") (pinfunction "NC_2") (pintype "bidirectional"))
    )
    (net (code "205") (name "unconnected-(U4-NC-Pad3)") (class "Default")
      (node (ref "U4") (pin "3") (pinfunction "NC_3") (pintype "bidirectional"))
    )
    (net (code "206") (name "unconnected-(U6-NC-Pad2)") (class "Default")
      (node (ref "U6") (pin "2") (pinfunction "NC_2") (pintype "bidirectional"))
    )
    (net (code "207") (name "unconnected-(U6-NC-Pad3)") (class "Default")
      (node (ref "U6") (pin "3") (pinfunction "NC_3") (pintype "bidirectional"))
    )
  )
)
